# 02_Face_InMain1V0.net
KiCad netlist of a schematic drawn in Altium Designer
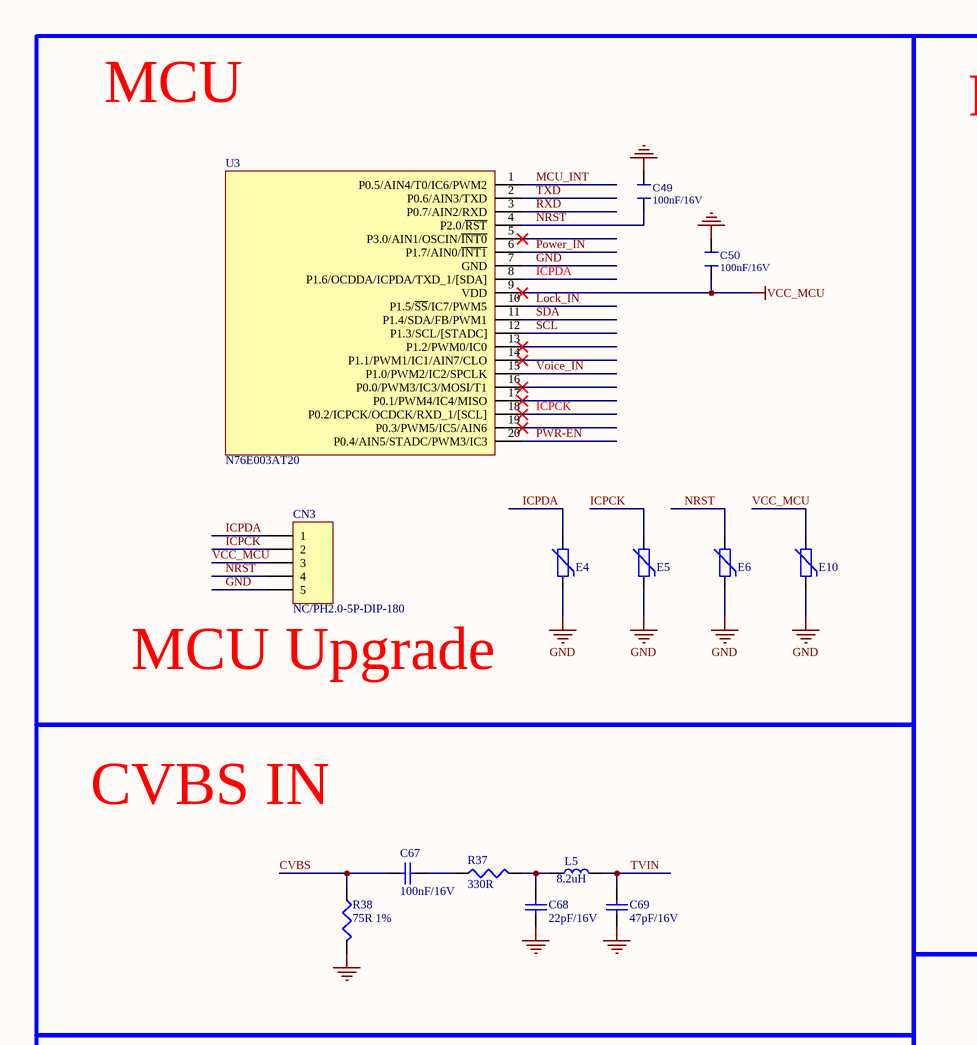
[diagram p0: 02_Face_InMain1V0.SchDoc, top left]
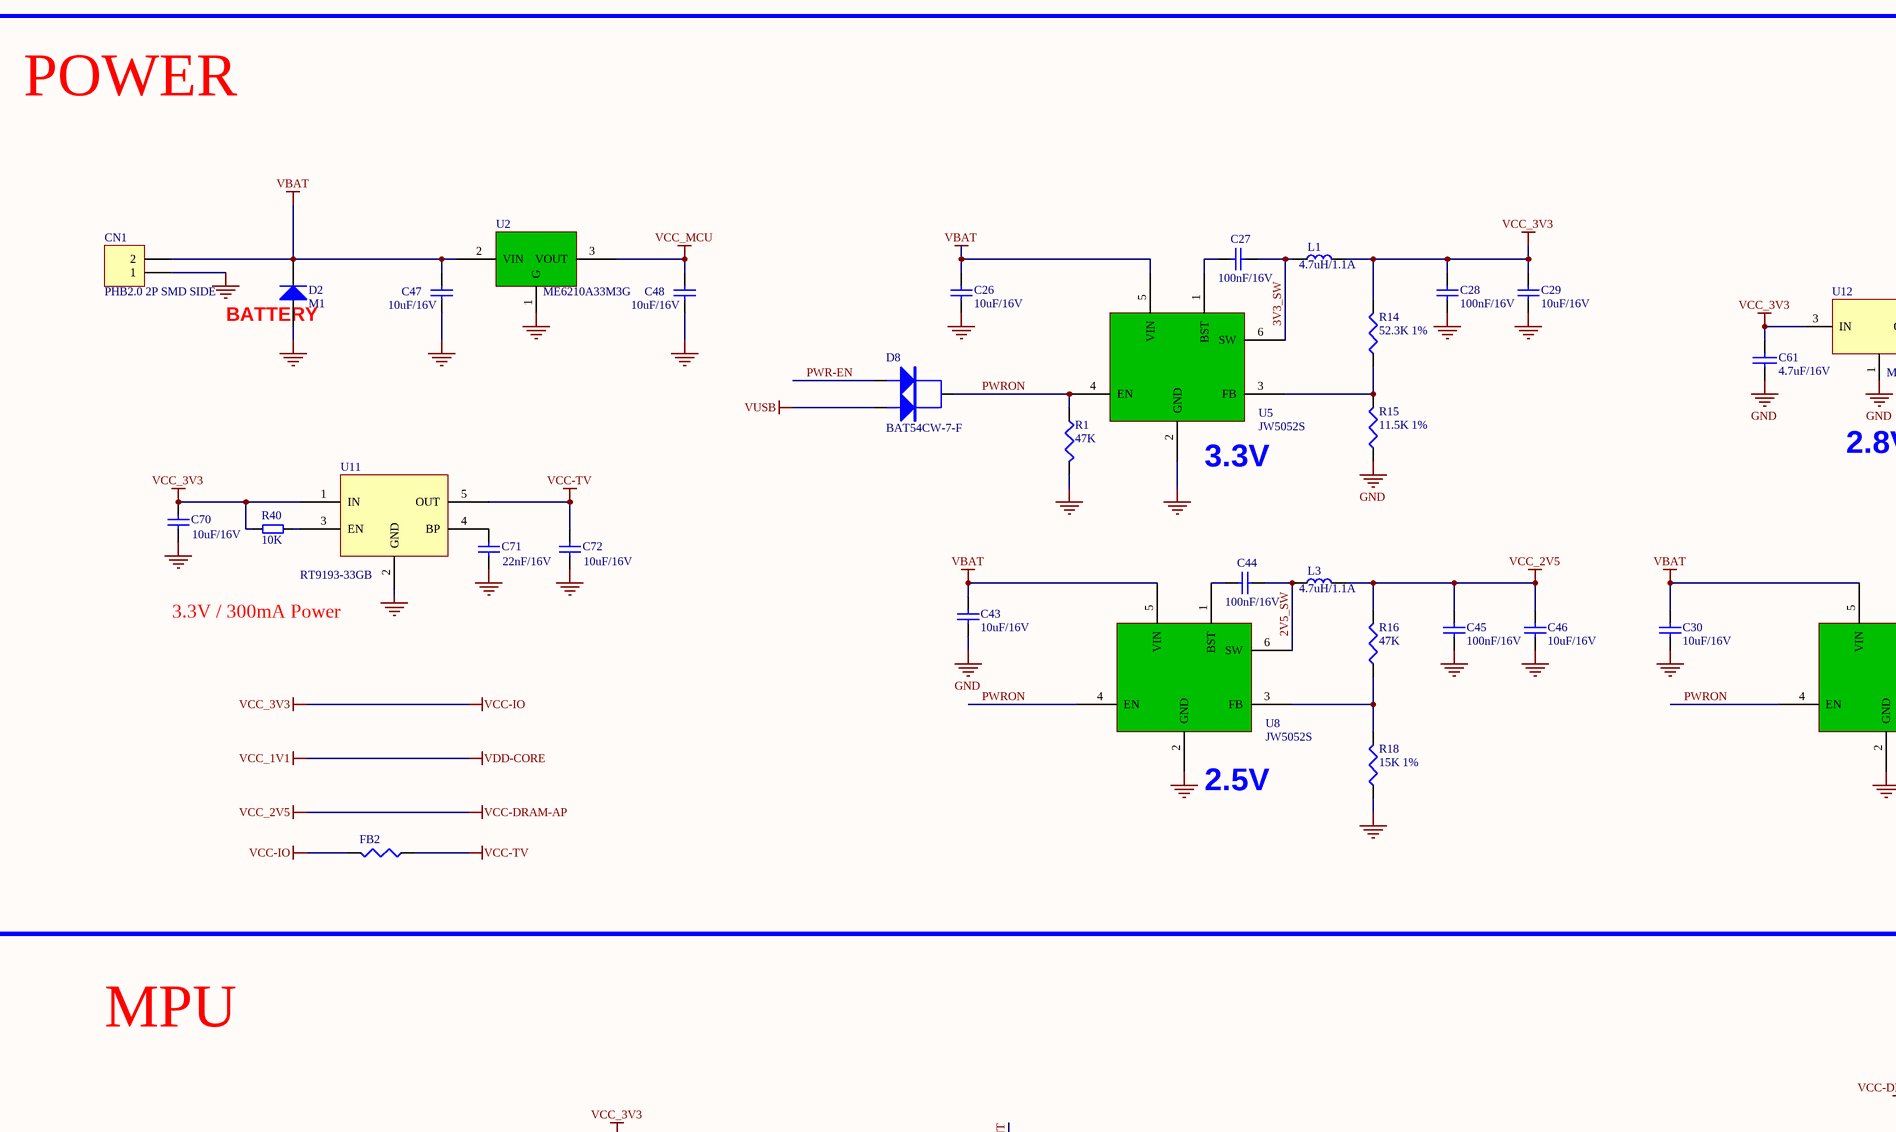
[diagram p1: 02_Face_InMain1V0.SchDoc, top middle]
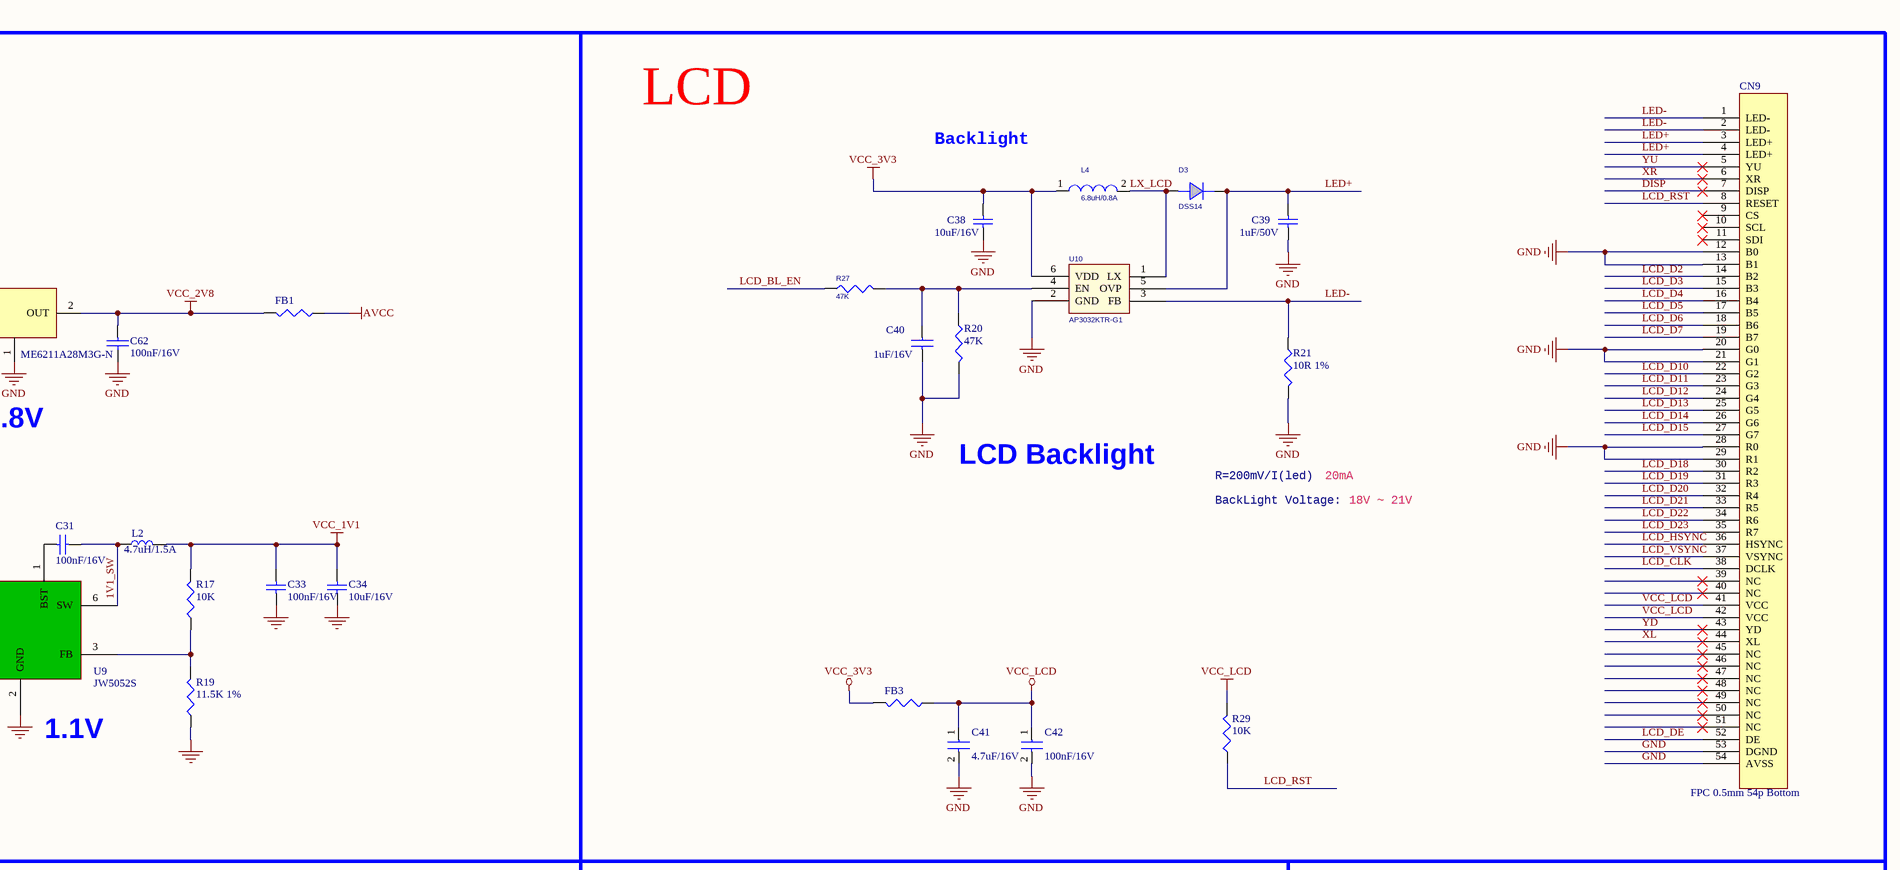
[diagram p2: 02_Face_InMain1V0.SchDoc, top right]
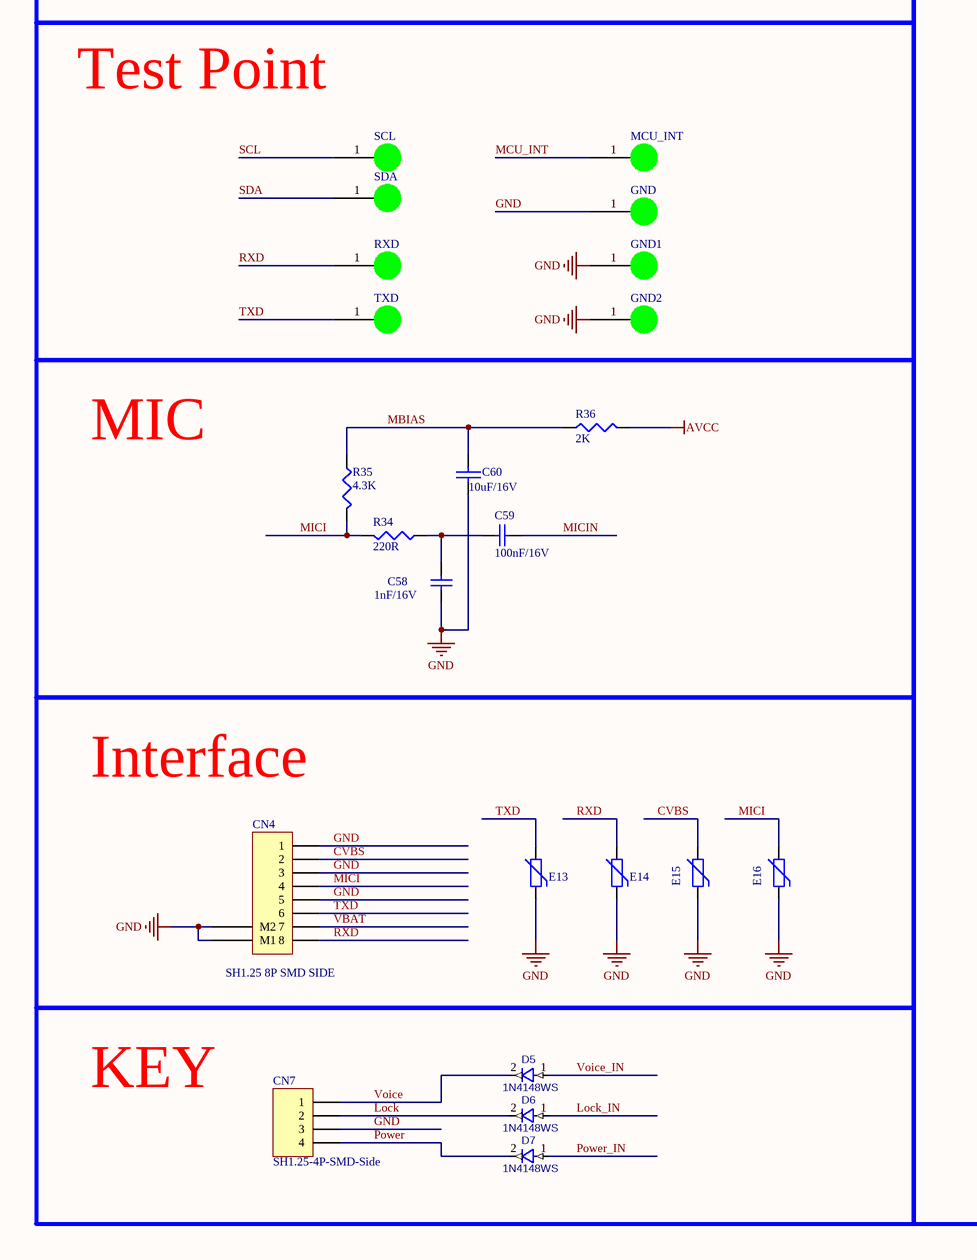
[diagram p3: 02_Face_InMain1V0.SchDoc, bottom left]
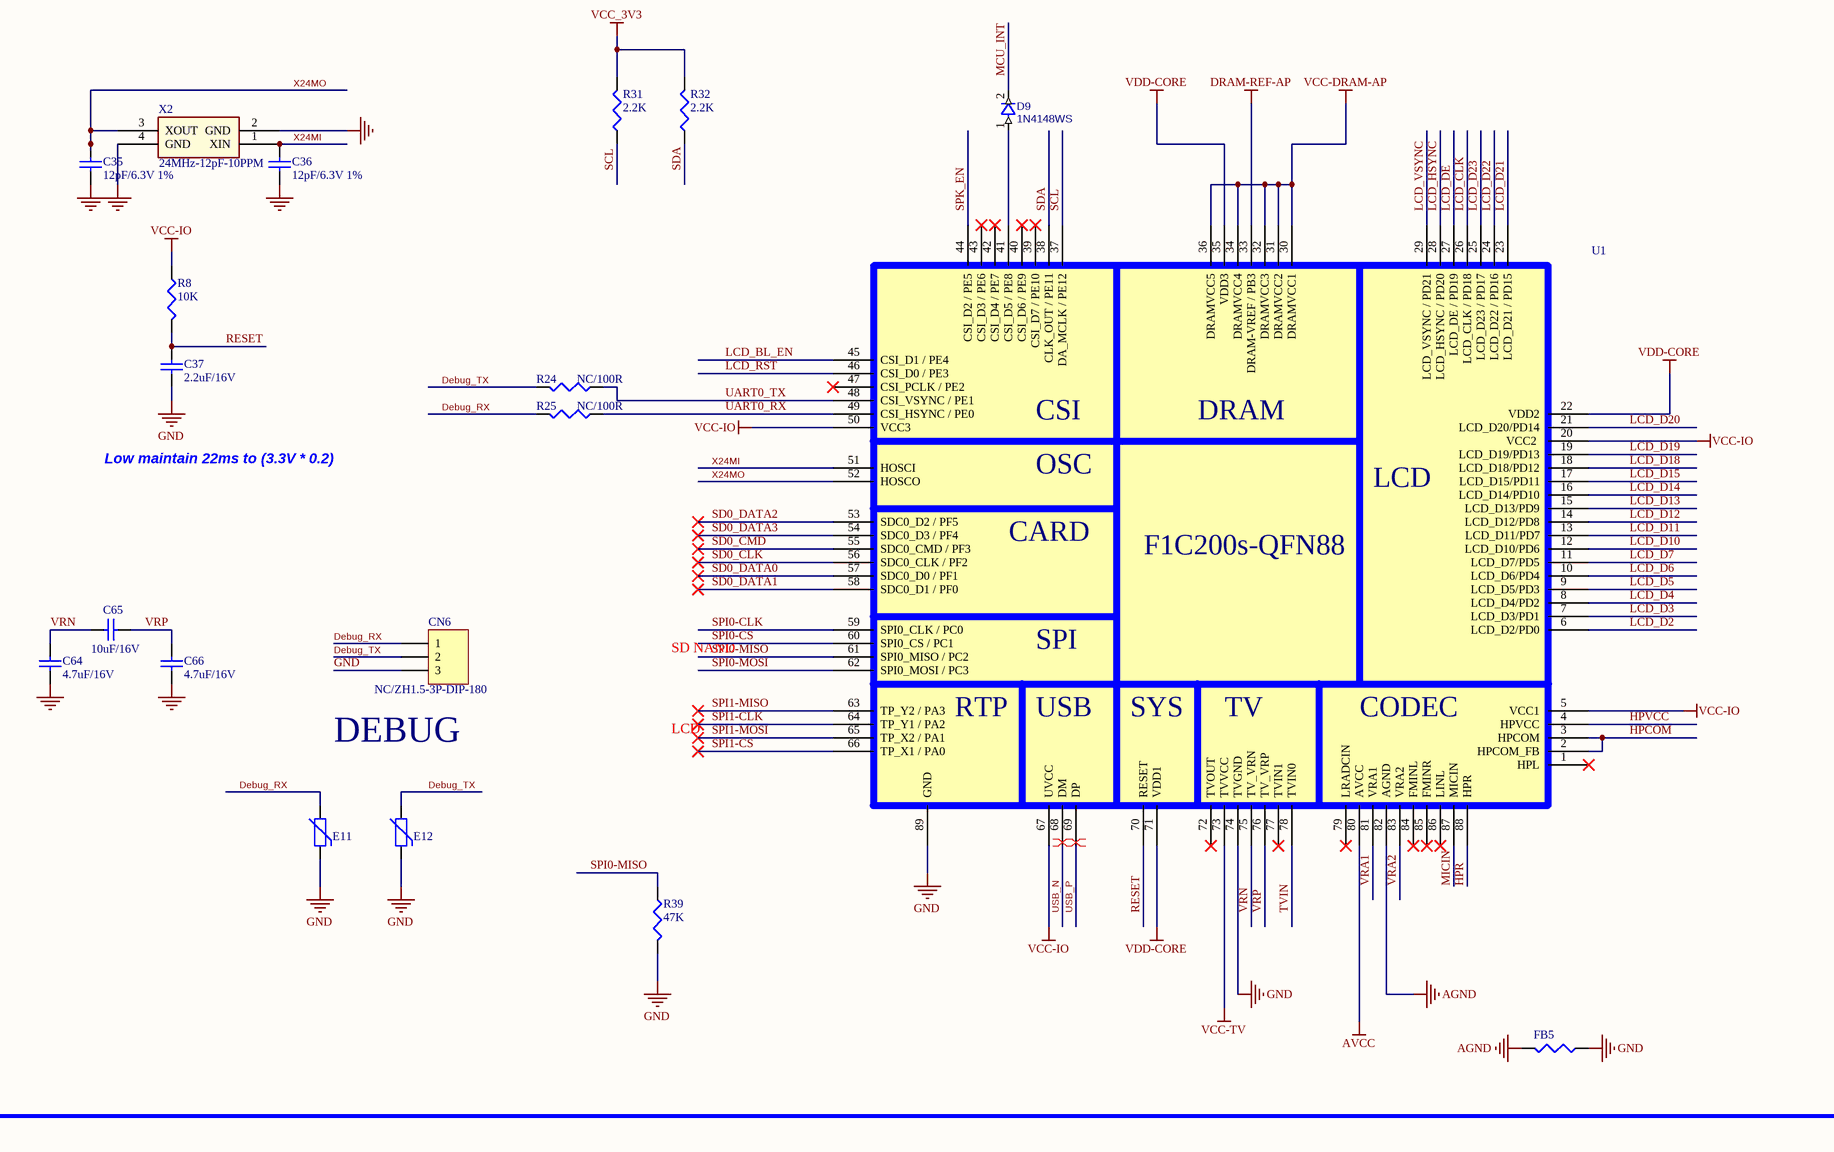
[diagram p4: 02_Face_InMain1V0.SchDoc, bottom middle]
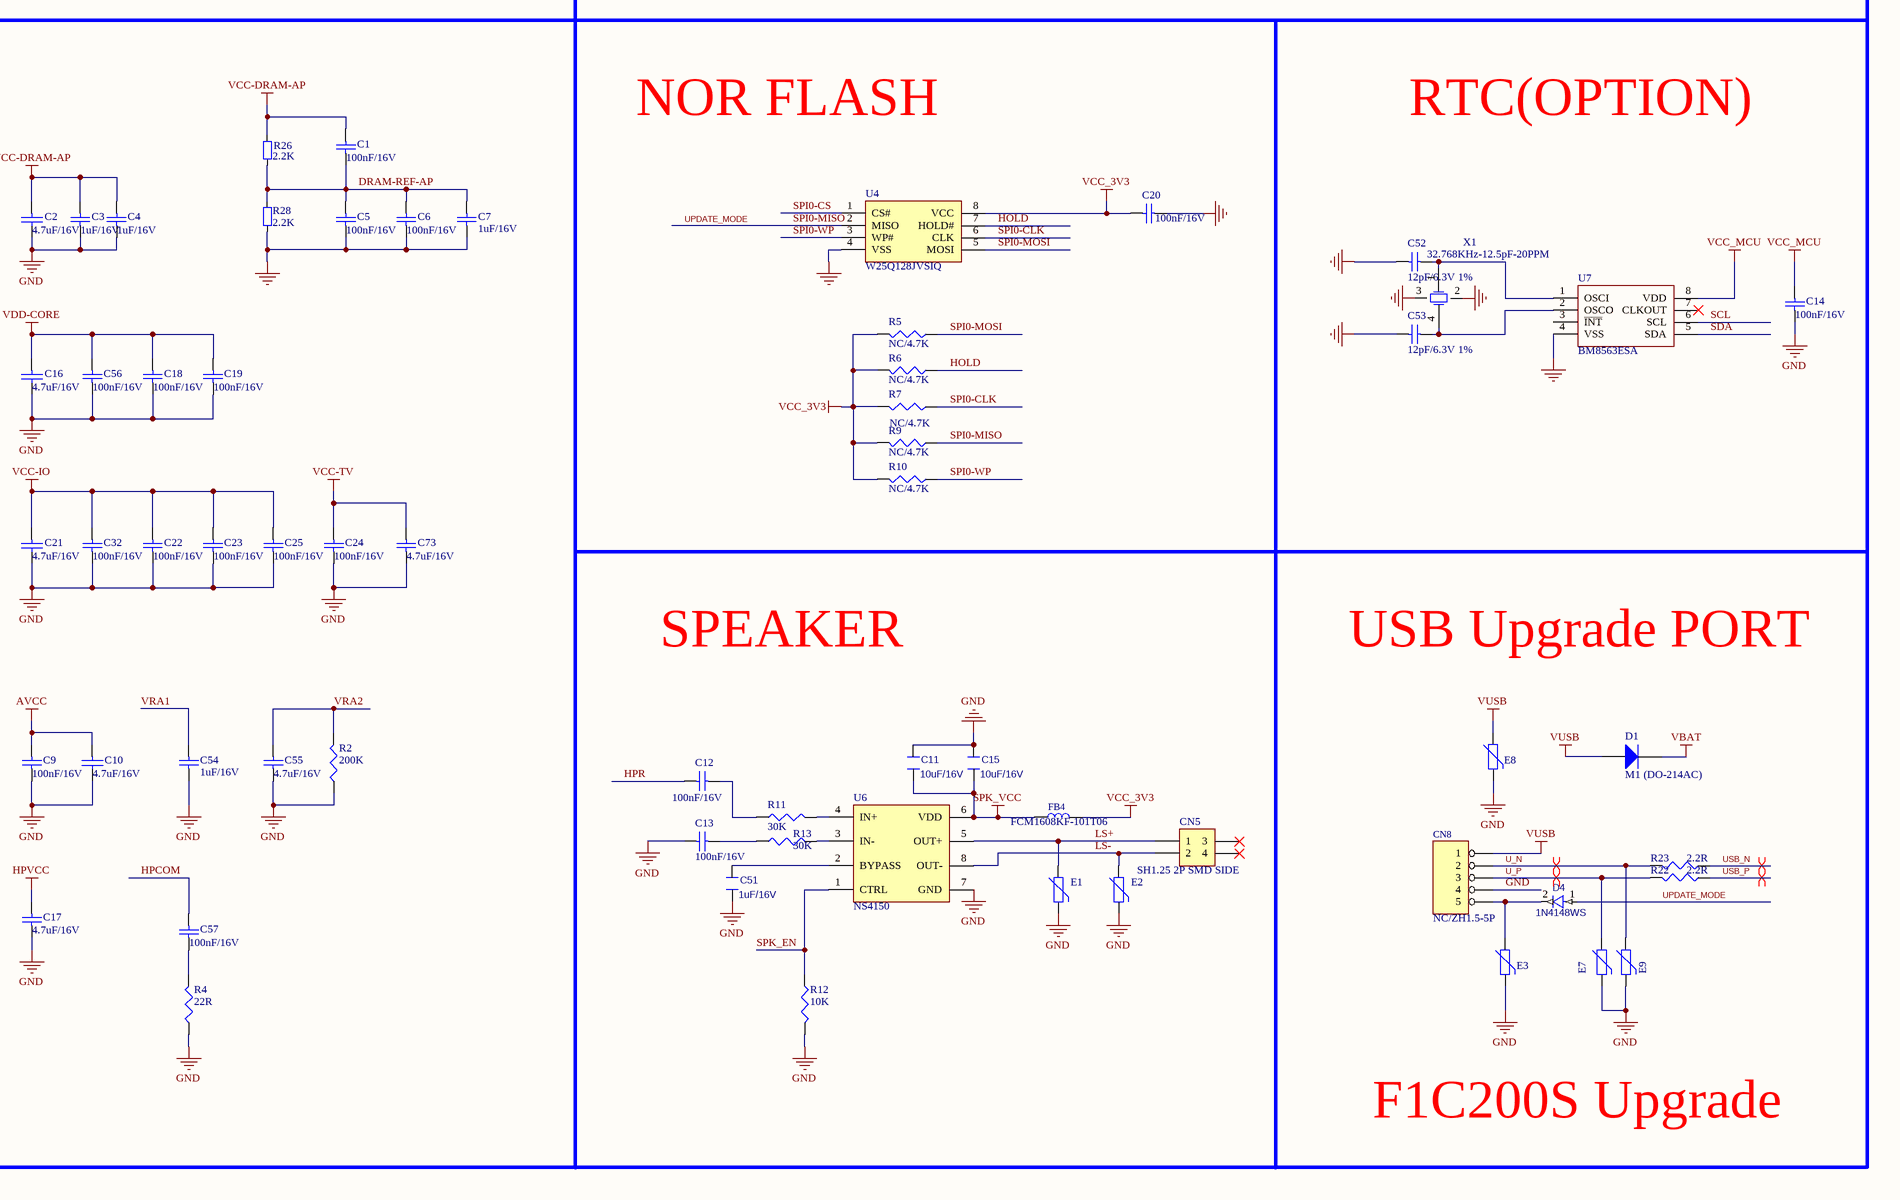
[diagram p5: 02_Face_InMain1V0.SchDoc, bottom right]

(export (version "E")
  (design (tool "Eeschema 10.0.6"))
  (components
    (comp (ref "C1")
      (value "100nF/16V")
      (footprint "C0402")
      (description "0.1uF  ±10% 16V X7R 0402 ROSH")
      (fields (field (name "PUBLISHER") "Altium Limited"))
      (libsource (lib "Miscellaneous Devices") (part "Cap"))
    )
    (comp (ref "C2")
      (value "4.7uF/16V")
      (footprint "C0603")
      (description "4.7uF/16V 10% 0603 X7R ROHS")
      (libsource (lib "*") (part "CAP"))
    )
    (comp (ref "C3")
      (value "1uF/16V")
      (footprint "C0402")
      (description "1uF/16V 10%  0402 X7R ROHS")
      (fields (field (name "PUBLISHER") "Altium Limited"))
      (libsource (lib "Miscellaneous Devices") (part "Cap"))
    )
    (comp (ref "C4")
      (value "1uF/16V")
      (footprint "C0402")
      (description "1uF/16V 10%  0402 X7R ROHS")
      (fields (field (name "PUBLISHER") "Altium Limited"))
      (libsource (lib "Miscellaneous Devices") (part "Cap"))
    )
    (comp (ref "C5")
      (value "100nF/16V")
      (footprint "C0402")
      (description "0.1uF  ±10% 16V X7R 0402 ROHS")
      (fields (field (name "PUBLISHER") "Altium Limited"))
      (libsource (lib "Miscellaneous Devices") (part "Cap"))
    )
    (comp (ref "C6")
      (value "100nF/16V")
      (footprint "C0402")
      (description "0.1uF  ±10% 16V X7R 0402 ROHS")
      (fields (field (name "PUBLISHER") "Altium Limited"))
      (libsource (lib "Miscellaneous Devices") (part "Cap"))
    )
    (comp (ref "C7")
      (value "1uF/16V")
      (footprint "C0402")
      (description "1uF/16V 10%  0402 X7R ROHS")
      (fields (field (name "PUBLISHER") "Altium Limited"))
      (libsource (lib "Miscellaneous Devices") (part "Cap"))
    )
    (comp (ref "C9")
      (value "100nF/16V")
      (footprint "C0402")
      (description "0.1uF  ±10% 16V X7R 0402 ROHS")
      (fields (field (name "PUBLISHER") "Altium Limited"))
      (libsource (lib "Miscellaneous Devices") (part "Cap"))
    )
    (comp (ref "C10")
      (value "4.7uF/16V")
      (footprint "C0603")
      (description "4.7uF/16V 10% 0603 X7R ROHS")
      (libsource (lib "*") (part "CAP"))
    )
    (comp (ref "C11")
      (value "10uF/16V")
      (footprint "C0805")
      (description "10uF/16V 10% 0805 X7R ROHS")
      (libsource (lib "LM") (part "CAP"))
    )
    (comp (ref "C12")
      (value "100nF/16V")
      (footprint "C0402")
      (description "0.1uF  ±10% 16V X7R 0402 ROSH")
      (fields (field (name "PUBLISHER") "Altium Limited"))
      (libsource (lib "Miscellaneous Devices") (part "Cap"))
    )
    (comp (ref "C13")
      (value "100nF/16V")
      (footprint "C0402")
      (description "0.1uF  ±10% 16V X7R 0402 ROSH")
      (fields (field (name "PUBLISHER") "Altium Limited"))
      (libsource (lib "Miscellaneous Devices") (part "Cap"))
    )
    (comp (ref "C14")
      (value "100nF/16V")
      (footprint "C0402")
      (description "0.1uF  ±10% 16V X7R 0402 ROSH")
      (fields (field (name "PUBLISHER") "Altium Limited"))
      (libsource (lib "Miscellaneous Devices") (part "Cap"))
    )
    (comp (ref "C15")
      (value "10uF/16V")
      (footprint "C0805")
      (description "10uF/16V 10% 0805 X7R ROHS")
      (libsource (lib "LM") (part "CAP"))
    )
    (comp (ref "C16")
      (value "4.7uF/16V")
      (footprint "C0603")
      (description "4.7uF/16V 10% 0603 X7R ROHS")
      (libsource (lib "*") (part "CAP"))
    )
    (comp (ref "C17")
      (value "4.7uF/16V")
      (footprint "C0603")
      (description "4.7uF/16V 10% 0603 X7R ROHS")
      (fields (field (name "PUBLISHER") "Altium Limited"))
      (libsource (lib "Miscellaneous Devices") (part "Cap"))
    )
    (comp (ref "C18")
      (value "100nF/16V")
      (footprint "C0402")
      (description "0.1uF  ±10% 16V X7R 0402 ROSH")
      (fields (field (name "PUBLISHER") "Altium Limited"))
      (libsource (lib "Miscellaneous Devices") (part "Cap"))
    )
    (comp (ref "C19")
      (value "100nF/16V")
      (footprint "C0402")
      (description "0.1uF  ±10% 16V X7R 0402 ROSH")
      (fields (field (name "PUBLISHER") "Altium Limited"))
      (libsource (lib "Miscellaneous Devices") (part "Cap"))
    )
    (comp (ref "C20")
      (value "100nF/16V")
      (footprint "C0402")
      (description "0.1uF  ±10% 16V X7R 0402 ROSH")
      (fields (field (name "PUBLISHER") "Altium Limited"))
      (libsource (lib "Miscellaneous Devices") (part "Cap"))
    )
    (comp (ref "C21")
      (value "4.7uF/16V")
      (footprint "C0603")
      (description "4.7uF/16V 10% 0603 X7R ROHS")
      (libsource (lib "*") (part "CAP"))
    )
    (comp (ref "C22")
      (value "100nF/16V")
      (footprint "C0402")
      (description "0.1uF  ±10% 16V X7R 0402 ROSH")
      (fields (field (name "PUBLISHER") "Altium Limited"))
      (libsource (lib "Miscellaneous Devices") (part "Cap"))
    )
    (comp (ref "C23")
      (value "100nF/16V")
      (footprint "C0402")
      (description "0.1uF  ±10% 16V X7R 0402 ROSH")
      (fields (field (name "PUBLISHER") "Altium Limited"))
      (libsource (lib "Miscellaneous Devices") (part "Cap"))
    )
    (comp (ref "C24")
      (value "100nF/16V")
      (footprint "C0402")
      (description "0.1uF  ±10% 16V X7R 0402 ROSH")
      (fields (field (name "PUBLISHER") "Altium Limited"))
      (libsource (lib "Miscellaneous Devices") (part "Cap"))
    )
    (comp (ref "C25")
      (value "100nF/16V")
      (footprint "C0402")
      (description "0.1uF  ±10% 16V X7R 0402 ROSH")
      (fields (field (name "PUBLISHER") "Altium Limited"))
      (libsource (lib "Miscellaneous Devices") (part "Cap"))
    )
    (comp (ref "C26")
      (value "10uF/16V")
      (footprint "C0805")
      (description "10uF/16V 10% 0805 X7R ROHS")
      (fields (field (name "PUBLISHER") "Altium Limited"))
      (libsource (lib "Miscellaneous Devices") (part "Cap"))
    )
    (comp (ref "C27")
      (value "100nF/16V")
      (footprint "C0402")
      (description "0.1uF  ±10% 16V X7R 0402 ROHS")
      (fields (field (name "PUBLISHER") "Altium Limited"))
      (libsource (lib "Miscellaneous Devices") (part "Cap"))
    )
    (comp (ref "C28")
      (value "100nF/16V")
      (footprint "C0402")
      (description "0.1uF  ±10% 16V X7R 0402 ROHS")
      (fields (field (name "PUBLISHER") "Altium Limited"))
      (libsource (lib "Miscellaneous Devices") (part "Cap"))
    )
    (comp (ref "C29")
      (value "10uF/16V")
      (footprint "C0805")
      (description "10uF/16V 10% 0805 X7R ROHS")
      (fields (field (name "PUBLISHER") "Altium Limited"))
      (libsource (lib "Miscellaneous Devices") (part "Cap"))
    )
    (comp (ref "C30")
      (value "10uF/16V")
      (footprint "C0805")
      (description "10uF/16V 10% 0805 X7R ROHS")
      (fields (field (name "PUBLISHER") "Altium Limited"))
      (libsource (lib "Miscellaneous Devices") (part "Cap"))
    )
    (comp (ref "C31")
      (value "100nF/16V")
      (footprint "C0402")
      (description "0.1uF  ±10% 16V X7R 0402 ROHS")
      (fields (field (name "PUBLISHER") "Altium Limited"))
      (libsource (lib "Miscellaneous Devices") (part "Cap"))
    )
    (comp (ref "C32")
      (value "100nF/16V")
      (footprint "C0402")
      (description "0.1uF  ±10% 16V X7R 0402 ROHS")
      (fields (field (name "PUBLISHER") "Altium Limited"))
      (libsource (lib "Miscellaneous Devices") (part "Cap"))
    )
    (comp (ref "C33")
      (value "100nF/16V")
      (footprint "C0402")
      (description "0.1uF  ±10% 16V X7R 0402 ROHS")
      (fields (field (name "PUBLISHER") "Altium Limited"))
      (libsource (lib "Miscellaneous Devices") (part "Cap"))
    )
    (comp (ref "C34")
      (value "10uF/16V")
      (footprint "C0805")
      (description "10uF/16V 10% 0805 X7R ROHS")
      (fields (field (name "PUBLISHER") "Altium Limited"))
      (libsource (lib "Miscellaneous Devices") (part "Cap"))
    )
    (comp (ref "C35")
      (value "12pF/6.3V 1%")
      (footprint "C0402")
      (description "12pF/6.3V 2% 0402 NPO ROHS")
      (fields (field (name "PUBLISHER") "Altium Limited"))
      (libsource (lib "Miscellaneous Devices") (part "Cap"))
    )
    (comp (ref "C36")
      (value "12pF/6.3V 1%")
      (footprint "C0402")
      (description "12pF/6.3V 2% 0402 NPO ROHS")
      (fields (field (name "PUBLISHER") "Altium Limited"))
      (libsource (lib "Miscellaneous Devices") (part "Cap"))
    )
    (comp (ref "C37")
      (value "2.2uF/16V")
      (footprint "C0402")
      (description "2.2uF/16V 10%  0402 X7R ROHS")
      (fields (field (name "PUBLISHER") "Altium Limited"))
      (libsource (lib "Miscellaneous Devices") (part "Cap"))
    )
    (comp (ref "C38")
      (value "10uF/16V")
      (footprint "C0805")
      (description "10uF/16V 10% 0805 X7R ROHS")
      (fields (field (name "PUBLISHER") "Altium Limited"))
      (libsource (lib "Miscellaneous Devices") (part "Cap"))
    )
    (comp (ref "C39")
      (value "1uF/50V")
      (footprint "C0805")
      (description "1uF/50V 10% 0805 X7R ROHS")
      (fields (field (name "PUBLISHER") "Altium Limited"))
      (libsource (lib "Miscellaneous Devices") (part "Cap"))
    )
    (comp (ref "C40")
      (value "1uF/16V")
      (footprint "C0402")
      (description "1uF/16V 10%  0402 X7R ROHS")
      (fields
        (field (name "VOLTAGE") "6.3V")
        (field (name "TOLERANCE") "10%")
        (field (name "CREATED BY") "JJJ")
      )
      (libsource (lib "") (part "CAP NP_Dup1_1"))
    )
    (comp (ref "C41")
      (value "4.7uF/16V")
      (footprint "C0603")
      (description "4.7uF/16V 10% 0603 X7R ROHS")
      (fields
        (field (name "VOLTAGE") "6.3V")
        (field (name "TOLERANCE") "10%")
        (field (name "CREATED BY") "JJJ")
      )
      (libsource (lib "*") (part "CAP NP_Dup1"))
    )
    (comp (ref "C42")
      (value "100nF/16V")
      (footprint "C0402")
      (description "0.1uF  ±10% 16V X7R 0402 ROHS")
      (fields
        (field (name "VOLTAGE") "6.3V")
        (field (name "TOLERANCE") "10%")
        (field (name "CREATED BY") "JJJ")
      )
      (libsource (lib "*") (part "CAP NP_Dup1"))
    )
    (comp (ref "C43")
      (value "10uF/16V")
      (footprint "C0805")
      (description "10uF/16V 10% 0805 X7R ROHS")
      (fields (field (name "PUBLISHER") "Altium Limited"))
      (libsource (lib "Miscellaneous Devices") (part "Cap"))
    )
    (comp (ref "C44")
      (value "100nF/16V")
      (footprint "C0402")
      (description "0.1uF  ±10% 16V X7R 0402 ROHS")
      (fields (field (name "PUBLISHER") "Altium Limited"))
      (libsource (lib "Miscellaneous Devices") (part "Cap"))
    )
    (comp (ref "C45")
      (value "100nF/16V")
      (footprint "C0402")
      (description "0.1uF  ±10% 16V X7R 0402 ROHS")
      (fields (field (name "PUBLISHER") "Altium Limited"))
      (libsource (lib "Miscellaneous Devices") (part "Cap"))
    )
    (comp (ref "C46")
      (value "10uF/16V")
      (footprint "C0805")
      (description "10uF/16V 10% 0805 X7R ROHS")
      (fields (field (name "PUBLISHER") "Altium Limited"))
      (libsource (lib "Miscellaneous Devices") (part "Cap"))
    )
    (comp (ref "C47")
      (value "10uF/16V")
      (footprint "C0805")
      (description "10uF/16V 10% 0805 X7R ROHS")
      (fields (field (name "PUBLISHER") "Altium Limited"))
      (libsource (lib "Miscellaneous Devices") (part "Cap"))
    )
    (comp (ref "C48")
      (value "10uF/16V")
      (footprint "C0805")
      (description "10uF/16V 10% 0805 X7R ROHS")
      (fields (field (name "PUBLISHER") "Altium Limited"))
      (libsource (lib "Miscellaneous Devices") (part "Cap"))
    )
    (comp (ref "C49")
      (value "100nF/16V")
      (footprint "C0402")
      (description "0.1uF  ±10% 16V X7R 0402 ROHS")
      (fields (field (name "ALTIUM_UNNAMED_1") "100nF/16V"))
      (libsource (lib "LM") (part "CAP"))
    )
    (comp (ref "C50")
      (value "100nF/16V")
      (footprint "C0402")
      (description "0.1uF  ±10% 16V X7R 0402 ROHS")
      (fields (field (name "ALTIUM_UNNAMED_1") "100nF/16V"))
      (libsource (lib "LM") (part "CAP"))
    )
    (comp (ref "C51")
      (value "1uF/16V")
      (footprint "C0402")
      (description "1uF ±10% 16V X7R 0402 ROSH")
      (libsource (lib "LM") (part "CAP"))
    )
    (comp (ref "C52")
      (value "12pF/6.3V 1%")
      (footprint "C0402")
      (description "12pF/6.3V 2% 0402 NPO ROHS")
      (fields (field (name "PUBLISHER") "Altium Limited"))
      (libsource (lib "Miscellaneous Devices") (part "Cap"))
    )
    (comp (ref "C53")
      (value "12pF/6.3V 1%")
      (footprint "C0402")
      (description "12pF/6.3V 2% 0402 NPO ROHS")
      (fields (field (name "PUBLISHER") "Altium Limited"))
      (libsource (lib "Miscellaneous Devices") (part "Cap"))
    )
    (comp (ref "C54")
      (value "1uF/16V")
      (footprint "C0402")
      (description "1uF/16V 10%  0402 X7R ROHS")
      (fields (field (name "PUBLISHER") "Altium Limited"))
      (libsource (lib "Miscellaneous Devices") (part "Cap"))
    )
    (comp (ref "C55")
      (value "4.7uF/16V")
      (footprint "C0603")
      (description "4.7uF/16V 10% 0603 X7R ROHS")
      (fields (field (name "PUBLISHER") "Altium Limited"))
      (libsource (lib "Miscellaneous Devices") (part "Cap"))
    )
    (comp (ref "C56")
      (value "100nF/16V")
      (footprint "C0402")
      (description "0.1uF  ±10% 16V X7R 0402 ROHS")
      (fields (field (name "PUBLISHER") "Altium Limited"))
      (libsource (lib "Miscellaneous Devices") (part "Cap"))
    )
    (comp (ref "C57")
      (value "100nF/16V")
      (footprint "C0402")
      (description "0.1uF  ±10% 16V X7R 0402 ROHS")
      (fields (field (name "PUBLISHER") "Altium Limited"))
      (libsource (lib "Miscellaneous Devices") (part "Cap"))
    )
    (comp (ref "C58")
      (value "1nF/16V")
      (footprint "C0402")
      (description "1nF  ±10% 16V X7R 0402 ROHS")
      (fields (field (name "PUBLISHER") "Altium Limited"))
      (libsource (lib "Miscellaneous Devices") (part "Cap"))
    )
    (comp (ref "C59")
      (value "100nF/16V")
      (footprint "C0402")
      (description "0.1uF  ±10% 16V X7R 0402 ROHS")
      (fields (field (name "PUBLISHER") "Altium Limited"))
      (libsource (lib "Miscellaneous Devices") (part "Cap"))
    )
    (comp (ref "C60")
      (value "10uF/16V")
      (footprint "C0805")
      (description "10uF/16V 10% 0805 X7R ROHS")
      (libsource (lib "*") (part "CAP"))
    )
    (comp (ref "C61")
      (value "4.7uF/16V")
      (footprint "C0603")
      (description "4.7uF/16V 10% 0603 X7R ROHS")
      (libsource (lib "FL01M1V5") (part "CAP"))
    )
    (comp (ref "C62")
      (value "100nF/16V")
      (footprint "C0402")
      (description "100nF/16V 10% 0402 X7R ROHS")
      (libsource (lib "FL01M1V5") (part "CAP"))
    )
    (comp (ref "C64")
      (value "4.7uF/16V")
      (footprint "C0603")
      (description "4.7uF/16V 10% 0603 X7R ROHS")
      (fields (field (name "PUBLISHER") "Altium Limited"))
      (libsource (lib "Miscellaneous Devices") (part "Cap"))
    )
    (comp (ref "C65")
      (value "10uF/16V")
      (footprint "C0805")
      (description "10uF/16V 10% 0805 X7R ROHS")
      (fields (field (name "PUBLISHER") "Altium Limited"))
      (libsource (lib "Miscellaneous Devices") (part "Cap"))
    )
    (comp (ref "C66")
      (value "4.7uF/16V")
      (footprint "C0603")
      (description "4.7uF/16V 10% 0603 X7R ROHS")
      (fields (field (name "PUBLISHER") "Altium Limited"))
      (libsource (lib "Miscellaneous Devices") (part "Cap"))
    )
    (comp (ref "C67")
      (value "100nF/16V")
      (footprint "C0402")
      (description "100nF/16V 10% 0402 X7R ROHS")
      (fields (field (name "PUBLISHER") "Altium Limited"))
      (libsource (lib "Miscellaneous Devices") (part "Cap"))
    )
    (comp (ref "C68")
      (value "22pF/16V")
      (footprint "C0402")
      (description "22pF/16V 10% 0402 X7R ROHS")
      (fields (field (name "PUBLISHER") "Altium Limited"))
      (libsource (lib "Miscellaneous Devices") (part "Cap"))
    )
    (comp (ref "C69")
      (value "47pF/16V")
      (footprint "C0402")
      (description "47pF/16V 10% 0402 X7R ROHS")
      (fields (field (name "PUBLISHER") "Altium Limited"))
      (libsource (lib "Miscellaneous Devices") (part "Cap"))
    )
    (comp (ref "C70")
      (value "10uF/16V")
      (footprint "C0805")
      (description "10uF/16V 10% 0805 X7R ROHS")
      (fields (field (name "PUBLISHER") "Altium Limited"))
      (libsource (lib "Miscellaneous Devices") (part "Cap"))
    )
    (comp (ref "C71")
      (value "22nF/16V")
      (footprint "C0402")
      (description "22nF/16V 10% 0402 X7R ROHS")
      (fields (field (name "PUBLISHER") "Altium Limited"))
      (libsource (lib "Miscellaneous Devices") (part "Cap"))
    )
    (comp (ref "C72")
      (value "10uF/16V")
      (footprint "C0805")
      (description "10uF/16V 10% 0805 X7R ROHS")
      (fields (field (name "PUBLISHER") "Altium Limited"))
      (libsource (lib "Miscellaneous Devices") (part "Cap"))
    )
    (comp (ref "C73")
      (value "4.7uF/16V")
      (footprint "C0603")
      (description "4.7uF/16V 10% 0603 X7R ROHS")
      (fields (field (name "PUBLISHER") "Altium Limited"))
      (libsource (lib "Miscellaneous Devices") (part "Cap"))
    )
    (comp (ref "CN1")
      (value "PHB2.0 2P SMD SIDE")
      (footprint "PH2.0_2P_SMD_SIDE")
      (description "PHB2.0 2P 90")
      (fields (field (name "PUBLISHER") "Altium Limited"))
      (libsource (lib "Miscellaneous Connectors") (part "Header 2"))
    )
    (comp (ref "CN3")
      (value "NC/PH2.0-5P-DIP-180")
      (footprint "HD2.0_5P")
      (description "PH2.0-5P-DIP-180")
      (fields (field (name "NAME1") "NC/PH2.0-5P-DIP-180"))
      (libsource (lib "LM") (part "Header5"))
    )
    (comp (ref "CN4")
      (value "SH1.25 8P SMD SIDE")
      (footprint "SH1.25_8P_SMD_SIDE")
      (description "FPC8_0.5")
      (fields (field (name "PUBLISHER") "Altium Limited"))
      (libsource (lib "S6X_1V0") (part "Header 8"))
    )
    (comp (ref "CN5")
      (value "SH1.25 2P SMD SIDE")
      (footprint "SH1.25_2P_SMD_SIDE")
      (libsource (lib "S8Main2V0") (part "Header2"))
    )
    (comp (ref "CN6")
      (value "NC/ZH1.5 3P")
      (footprint "HD1.5_3P")
      (description "ZH1.5mm 3P")
      (fields (field (name "NAME1") "NC/ZH1.5-3P-DIP-180"))
      (libsource (lib "LM") (part "Header3"))
    )
    (comp (ref "CN7")
      (value "SH1.25-4P-SMD-TOP")
      (footprint "SH1.25_4P_SMd_SIDE")
      (fields (field (name "NAME1") "SH1.25-4P-SMD-Side"))
      (libsource (lib "LM") (part "Header4"))
    )
    (comp (ref "CN8")
      (value "NC/ZH1.5-5P")
      (footprint "HD5_1.5")
      (description "ZH1.5mm 5P")
      (libsource (lib "*") (part "HEADER 5"))
    )
    (comp (ref "CN9")
      (value "FPC 0.5mm 54p Bottom")
      (footprint "FPC54_0.5_BOTTOM_Clamshell-1")
      (libsource (lib "*") (part "CON54"))
    )
    (comp (ref "D1")
      (value "M1 (DO-214AC)")
      (footprint "DO-214AC")
      (libsource (lib "LM") (part "M2 (DO-214AC)"))
    )
    (comp (ref "D2")
      (value "M1 (DO-214AC)")
      (footprint "DO-214AC")
      (fields (field (name "ALTIUM_UNNAMED_1") "M1"))
      (libsource (lib "LM") (part "M2 (DO-214AC)"))
    )
    (comp (ref "D3") (value "DSS14") (footprint "SOD-123FL") (libsource (lib "*") (part "D_0")))
    (comp (ref "D4")
      (value "1N4148WS")
      (footprint "SOD-323")
      (description "1N4148WS (SOD-323)")
      (libsource (lib "*") (part "1N4500"))
    )
    (comp (ref "D5")
      (value "1N4148WS")
      (footprint "SOD-323")
      (description "1N4148WS (SOD-323)")
      (libsource (lib "*") (part "1N4500"))
    )
    (comp (ref "D6")
      (value "1N4148WS")
      (footprint "SOD-323")
      (description "1N4148WS (SOD-323)")
      (libsource (lib "*") (part "1N4500"))
    )
    (comp (ref "D7")
      (value "1N4148WS")
      (footprint "SOD-323")
      (description "1N4148WS (SOD-323)")
      (libsource (lib "*") (part "1N4500"))
    )
    (comp (ref "D8")
      (value "BAT54CW-7-F (SOT-323)")
      (footprint "sot323")
      (fields (field (name "ALTIUM_UNNAMED_1") "BAT54CW-7-F"))
      (libsource (lib "LM") (part "BAT54CW-KL7"))
    )
    (comp (ref "D9")
      (value "1N4148WS")
      (footprint "SOD-323")
      (description "1N4148WS (SOD-323)")
      (libsource (lib "*") (part "1N4500"))
    )
    (comp (ref "E1")
      (value "SFI0402-050E330NP-LF")
      (footprint "R0402")
      (libsource (lib "ZhuhaiSch") (part "VARISTOR"))
    )
    (comp (ref "E2")
      (value "SFI0402-050E330NP-LF")
      (footprint "R0402")
      (libsource (lib "ZhuhaiSch") (part "VARISTOR"))
    )
    (comp (ref "E3")
      (value "SFI0402-050E330NP-LF")
      (footprint "R0402")
      (libsource (lib "ZhuhaiSch") (part "VARISTOR"))
    )
    (comp (ref "E4")
      (value "SFI0402-050E330NP-LF")
      (footprint "R0402")
      (libsource (lib "ZhuhaiSch") (part "VARISTOR"))
    )
    (comp (ref "E5")
      (value "SFI0402-050E330NP-LF")
      (footprint "R0402")
      (libsource (lib "ZhuhaiSch") (part "VARISTOR"))
    )
    (comp (ref "E6")
      (value "SFI0402-050E330NP-LF")
      (footprint "R0402")
      (libsource (lib "ZhuhaiSch") (part "VARISTOR"))
    )
    (comp (ref "E7")
      (value "SLESDL0402-24")
      (footprint "R0402")
      (libsource (lib "ZhuhaiSch") (part "VARISTOR"))
    )
    (comp (ref "E8")
      (value "SFI0402-050E330NP-LF")
      (footprint "R0402")
      (libsource (lib "ZhuhaiSch") (part "VARISTOR"))
    )
    (comp (ref "E9")
      (value "SLESDL0402-24")
      (footprint "R0402")
      (libsource (lib "ZhuhaiSch") (part "VARISTOR"))
    )
    (comp (ref "E10")
      (value "SFI0402-050E330NP-LF")
      (footprint "R0402")
      (libsource (lib "ZhuhaiSch") (part "VARISTOR"))
    )
    (comp (ref "E11")
      (value "NC/SFI0402-050E330NP-LF")
      (footprint "R0402")
      (description "SFI0402-050E330NP-LF")
      (libsource (lib "ZhuhaiSch") (part "VARISTOR"))
    )
    (comp (ref "E12")
      (value "NC/SFI0402-050E330NP-LF")
      (footprint "R0402")
      (description "SFI0402-050E330NP-LF")
      (libsource (lib "ZhuhaiSch") (part "VARISTOR"))
    )
    (comp (ref "E13")
      (value "SFI0402-050E330NP-LF")
      (footprint "R0402")
      (libsource (lib "ZhuhaiSch") (part "VARISTOR"))
    )
    (comp (ref "E14")
      (value "SFI0402-050E330NP-LF")
      (footprint "R0402")
      (libsource (lib "ZhuhaiSch") (part "VARISTOR"))
    )
    (comp (ref "E15")
      (value "SLESDL0402-24")
      (footprint "R0402")
      (libsource (lib "ZhuhaiSch") (part "VARISTOR"))
    )
    (comp (ref "E16")
      (value "SLESDL0402-24")
      (footprint "R0402")
      (libsource (lib "ZhuhaiSch") (part "VARISTOR"))
    )
    (comp (ref "FB1")
      (value "FB_100R")
      (footprint "R0603")
      (description "FCM1608KF-101T06")
      (fields
        (field (name "TOLERANCE") "5%")
        (field (name "MANUFACTURER") "YAGEO")
        (field (name "CREATED BY") "YTL")
      )
      (libsource (lib "*") (part "RESISTOR_Dup1"))
    )
    (comp (ref "FB2")
      (value "NC/FB_100R")
      (footprint "R0603")
      (description "FCM1608KF-101T06")
      (fields
        (field (name "TOLERANCE") "5%")
        (field (name "MANUFACTURER") "YAGEO")
        (field (name "CREATED BY") "YTL")
      )
      (libsource (lib "*") (part "RESISTOR_Dup1"))
    )
    (comp (ref "FB3")
      (value "FB_100R")
      (footprint "R0603")
      (description "FCM1608KF-101T06")
      (fields
        (field (name "TOLERANCE") "5%")
        (field (name "MANUFACTURER") "YAGEO")
        (field (name "CREATED BY") "YTL")
      )
      (libsource (lib "*") (part "RESISTOR_Dup1"))
    )
    (comp (ref "FB4") (value "FCM1608KF-101T06") (footprint "R0603") (libsource (lib "LM") (part "INDUCTOR")))
    (comp (ref "FB5")
      (value "FB_100R")
      (footprint "R0603")
      (description "FCM1608KF-101T06")
      (fields
        (field (name "TOLERANCE") "5%")
        (field (name "MANUFACTURER") "YAGEO")
        (field (name "CREATED BY") "YTL")
      )
      (libsource (lib "*") (part "RESISTOR_Dup1"))
    )
    (comp (ref "GND")
      (value "Test Point")
      (footprint "Test Point")
      (libsource (lib "VD_DES3V0") (part "Test Point"))
    )
    (comp (ref "GND1")
      (value "Test Point")
      (footprint "Test Pad")
      (libsource (lib "VD_DES3V0") (part "Test Point"))
    )
    (comp (ref "GND2")
      (value "Test Point")
      (footprint "Test Pad")
      (libsource (lib "VD_DES3V0") (part "Test Point"))
    )
    (comp (ref "L1")
      (value "4.7uH/1.1A")
      (footprint "CD32")
      (description "SWPA3015S4R7MT(4.7uH@1.1A DCR<0.125R)")
      (libsource (lib "FL01M1V5") (part "Inductor"))
    )
    (comp (ref "L2")
      (value "4.7uH/1.5A")
      (footprint "CD32")
      (description "SWPA3015S4R7MT(4.7uH@1.1A DCR<0.125R)")
      (libsource (lib "FL01M1V5") (part "Inductor"))
    )
    (comp (ref "L3")
      (value "4.7uH/1.1A")
      (footprint "CD32")
      (description "SWPA3015S4R7MT(4.7uH@1.1A DCR<0.125R)")
      (libsource (lib "FL01M1V5") (part "Inductor"))
    )
    (comp (ref "L4")
      (value "6.8uH/0.8A")
      (footprint "CD32")
      (description "SWPA3015S6R8MT(6.8uH@0.85A DCR<0.200R)")
      (libsource (lib "*") (part "INDUCTOR_Dup1"))
    )
    (comp (ref "L5")
      (value "8.2uH")
      (footprint "R0603")
      (description "SDFL1608S8R2KTF(8.2uH@5mA DCR<2.1R)")
      (libsource (lib "S10_5V1") (part "Inductor"))
    )
    (comp (ref "MCU_INT")
      (value "Test Point")
      (footprint "Test Point")
      (libsource (lib "VD_DES3V0") (part "Test Point"))
    )
    (comp (ref "R1")
      (value "47K")
      (footprint "R0402")
      (description "47K +/-1% 1/16W 0402 ROHS")
      (fields
        (field (name "TOLERANCE") "5%")
        (field (name "MANUFACTURER") "YAGEO")
        (field (name "CREATED BY") "YTL")
      )
      (libsource (lib "*") (part "RESISTOR_Dup1"))
    )
    (comp (ref "R2")
      (value "200K")
      (footprint "R0402")
      (description "200K +/-5% 1/16W 0402 ROHS")
      (fields
        (field (name "TOLERANCE") "5%")
        (field (name "MANUFACTURER") "YAGEO")
        (field (name "CREATED BY") "YTL")
      )
      (libsource (lib "*") (part "RESISTOR_Dup1"))
    )
    (comp (ref "R4")
      (value "22R")
      (footprint "R0402")
      (description "22R +/-5% 1/16W 0402 ROHS")
      (fields
        (field (name "TOLERANCE") "5%")
        (field (name "MANUFACTURER") "YAGEO")
        (field (name "CREATED BY") "YTL")
      )
      (libsource (lib "*") (part "RESISTOR_Dup1"))
    )
    (comp (ref "R5")
      (value "NC/4.7K")
      (footprint "R0402")
      (description "4.7K +/-5% 1/16W 0402 ROHS")
      (fields
        (field (name "TOLERANCE") "5%")
        (field (name "MANUFACTURER") "YAGEO")
        (field (name "CREATED BY") "YTL")
      )
      (libsource (lib "*") (part "RESISTOR_Dup1"))
    )
    (comp (ref "R6")
      (value "NC/4.7K")
      (footprint "R0402")
      (description "4.7K +/-5% 1/16W 0402 ROHS")
      (fields
        (field (name "TOLERANCE") "5%")
        (field (name "MANUFACTURER") "YAGEO")
        (field (name "CREATED BY") "YTL")
      )
      (libsource (lib "*") (part "RESISTOR_Dup1"))
    )
    (comp (ref "R7")
      (value "NC/4.7K")
      (footprint "R0402")
      (description "4.7K +/-5% 1/16W 0402 ROHS")
      (fields
        (field (name "TOLERANCE") "5%")
        (field (name "MANUFACTURER") "YAGEO")
        (field (name "CREATED BY") "YTL")
      )
      (libsource (lib "*") (part "RESISTOR_Dup1"))
    )
    (comp (ref "R8")
      (value "10K")
      (footprint "R0402")
      (description "10K +/-1% 1/16W 0402 ROHS")
      (fields
        (field (name "TOLERANCE") "5%")
        (field (name "MANUFACTURER") "YAGEO")
        (field (name "CREATED BY") "YTL")
      )
      (libsource (lib "*") (part "RESISTOR_Dup1"))
    )
    (comp (ref "R9")
      (value "NC/4.7K")
      (footprint "R0402")
      (description "4.7K +/-5% 1/16W 0402 ROHS")
      (fields
        (field (name "TOLERANCE") "5%")
        (field (name "MANUFACTURER") "YAGEO")
        (field (name "CREATED BY") "YTL")
      )
      (libsource (lib "*") (part "RESISTOR_Dup1"))
    )
    (comp (ref "R10")
      (value "NC/4.7K")
      (footprint "R0402")
      (description "4.7K +/-5% 1/16W 0402 ROHS")
      (fields
        (field (name "TOLERANCE") "5%")
        (field (name "MANUFACTURER") "YAGEO")
        (field (name "CREATED BY") "YTL")
      )
      (libsource (lib "*") (part "RESISTOR_Dup1"))
    )
    (comp (ref "R11")
      (value "30K")
      (footprint "R0402")
      (description "30K +/-5% 1/16W 0402 ROHS")
      (fields
        (field (name "TOLERANCE") "5%")
        (field (name "MANUFACTURER") "YAGEO")
        (field (name "CREATED BY") "YTL")
      )
      (libsource (lib "*") (part "RESISTOR_Dup1"))
    )
    (comp (ref "R12")
      (value "10K")
      (footprint "R0402")
      (description "10K +/-1% 1/16W 0402 ROHS")
      (fields
        (field (name "TOLERANCE") "5%")
        (field (name "MANUFACTURER") "YAGEO")
        (field (name "CREATED BY") "YTL")
      )
      (libsource (lib "*") (part "RESISTOR_Dup1"))
    )
    (comp (ref "R13")
      (value "30K")
      (footprint "R0402")
      (description "30K +/-5% 1/16W 0402 ROHS")
      (fields
        (field (name "TOLERANCE") "5%")
        (field (name "MANUFACTURER") "YAGEO")
        (field (name "CREATED BY") "YTL")
      )
      (libsource (lib "*") (part "RESISTOR_Dup1"))
    )
    (comp (ref "R14")
      (value "52.3K 1%")
      (footprint "R0402")
      (description "52.3K +/-1% 1/16W 0402 ROHS")
      (fields
        (field (name "TOLERANCE") "5%")
        (field (name "MANUFACTURER") "YAGEO")
        (field (name "CREATED BY") "YTL")
      )
      (libsource (lib "*") (part "RESISTOR_Dup1"))
    )
    (comp (ref "R15")
      (value "11.5K 1%")
      (footprint "R0402")
      (description "11.5K +/-1% 1/16W 0402 ROHS")
      (fields
        (field (name "TOLERANCE") "5%")
        (field (name "MANUFACTURER") "YAGEO")
        (field (name "CREATED BY") "YTL")
      )
      (libsource (lib "*") (part "RESISTOR_Dup1"))
    )
    (comp (ref "R16")
      (value "47K")
      (footprint "R0402")
      (description "47K +/-1% 1/16W 0402 ROHS")
      (fields
        (field (name "TOLERANCE") "5%")
        (field (name "MANUFACTURER") "YAGEO")
        (field (name "CREATED BY") "YTL")
      )
      (libsource (lib "*") (part "RESISTOR_Dup1"))
    )
    (comp (ref "R17")
      (value "10K")
      (footprint "R0402")
      (description "10K +/-1% 1/16W 0402 ROHS")
      (fields
        (field (name "TOLERANCE") "5%")
        (field (name "MANUFACTURER") "YAGEO")
        (field (name "CREATED BY") "YTL")
      )
      (libsource (lib "*") (part "RESISTOR_Dup1"))
    )
    (comp (ref "R18")
      (value "15K 1%")
      (footprint "R0402")
      (description "15K +/-1% 1/16W 0402 ROHS")
      (fields
        (field (name "TOLERANCE") "5%")
        (field (name "MANUFACTURER") "YAGEO")
        (field (name "CREATED BY") "YTL")
      )
      (libsource (lib "*") (part "RESISTOR_Dup1"))
    )
    (comp (ref "R19")
      (value "11.5K 1%")
      (footprint "R0402")
      (description "11.5K +/-1% 1/16W 0402 ROHS")
      (fields
        (field (name "TOLERANCE") "5%")
        (field (name "MANUFACTURER") "YAGEO")
        (field (name "CREATED BY") "YTL")
      )
      (libsource (lib "*") (part "RESISTOR_Dup1"))
    )
    (comp (ref "R20")
      (value "47K")
      (footprint "R0402")
      (description "47K +/-1% 1/16W 0402 ROHS")
      (fields
        (field (name "TOLERANCE") "5%")
        (field (name "MANUFACTURER") "YAGEO")
        (field (name "CREATED BY") "YTL")
      )
      (libsource (lib "*") (part "RESISTOR_Dup1"))
    )
    (comp (ref "R21")
      (value "10R 1%")
      (footprint "R0603")
      (description "10R +/-1% 1/10W 0603 ROHS")
      (fields
        (field (name "TOLERANCE") "5%")
        (field (name "MANUFACTURER") "YAGEO")
        (field (name "CREATED BY") "YTL")
      )
      (libsource (lib "*") (part "RESISTOR_Dup1"))
    )
    (comp (ref "R22")
      (value "2.2R")
      (footprint "R0402")
      (description "2.2R +/-5% 1/16W 0402 ROHS")
      (fields
        (field (name "TOLERANCE") "5%")
        (field (name "MANUFACTURER") "YAGEO")
        (field (name "CREATED BY") "YTL")
      )
      (libsource (lib "*") (part "RESISTOR_Dup1"))
    )
    (comp (ref "R23")
      (value "2.2R")
      (footprint "R0402")
      (description "2.2R +/-5% 1/16W 0402 ROHS")
      (fields
        (field (name "TOLERANCE") "5%")
        (field (name "MANUFACTURER") "YAGEO")
        (field (name "CREATED BY") "YTL")
      )
      (libsource (lib "*") (part "RESISTOR_Dup1"))
    )
    (comp (ref "R24")
      (value "NC/100R")
      (footprint "R0402")
      (description "100R +/-5% 1/16W 0402 ROHS")
      (fields
        (field (name "TOLERANCE") "5%")
        (field (name "MANUFACTURER") "YAGEO")
        (field (name "CREATED BY") "YTL")
      )
      (libsource (lib "*") (part "RESISTOR_Dup1"))
    )
    (comp (ref "R25")
      (value "NC/100R")
      (footprint "R0402")
      (description "100R +/-5% 1/16W 0402 ROHS")
      (fields
        (field (name "TOLERANCE") "5%")
        (field (name "MANUFACTURER") "YAGEO")
        (field (name "CREATED BY") "YTL")
      )
      (libsource (lib "*") (part "RESISTOR_Dup1"))
    )
    (comp (ref "R26")
      (value "2.2K")
      (footprint "R0402")
      (description "2.2K +/-1% 1/16W 0402 ROHS")
      (fields (field (name "PUBLISHER") "Altium Limited"))
      (libsource (lib "FL01M1V5") (part "RES2"))
    )
    (comp (ref "R27")
      (value "47K")
      (footprint "R0402")
      (description "47K +/-1% 1/16W 0402 ROHS")
      (libsource (lib "*") (part "RESISTOR_Dup2"))
    )
    (comp (ref "R28")
      (value "2.2K")
      (footprint "R0402")
      (description "2.2K +/-1% 1/16W 0402 ROHS")
      (fields (field (name "PUBLISHER") "Altium Limited"))
      (libsource (lib "FL01M1V5") (part "RES2"))
    )
    (comp (ref "R29")
      (value "10K")
      (footprint "R0402")
      (description "10K +/-1% 1/16W 0402 ROHS")
      (fields
        (field (name "TOLERANCE") "5%")
        (field (name "MANUFACTURER") "YAGEO")
        (field (name "CREATED BY") "YTL")
      )
      (libsource (lib "*") (part "RESISTOR_Dup1"))
    )
    (comp (ref "R31")
      (value "2.2K")
      (footprint "R0402")
      (description "2.2K +/-1% 1/16W 0402 ROHS")
      (fields
        (field (name "TOLERANCE") "5%")
        (field (name "MANUFACTURER") "YAGEO")
        (field (name "CREATED BY") "YTL")
      )
      (libsource (lib "*") (part "RESISTOR_Dup1"))
    )
    (comp (ref "R32")
      (value "2.2K")
      (footprint "R0402")
      (description "2.2K +/-1% 1/16W 0402 ROHS")
      (fields
        (field (name "TOLERANCE") "5%")
        (field (name "MANUFACTURER") "YAGEO")
        (field (name "CREATED BY") "YTL")
      )
      (libsource (lib "*") (part "RESISTOR_Dup1"))
    )
    (comp (ref "R34")
      (value "220R")
      (footprint "R0402")
      (description "220R +/-1% 1/16W 0402 ROHS")
      (fields
        (field (name "TOLERANCE") "5%")
        (field (name "MANUFACTURER") "YAGEO")
        (field (name "CREATED BY") "YTL")
      )
      (libsource (lib "*") (part "RESISTOR_Dup1"))
    )
    (comp (ref "R35")
      (value "4.3K")
      (footprint "R0402")
      (description "4.3K +/-1% 1/16W 0402 ROHS")
      (fields
        (field (name "TOLERANCE") "5%")
        (field (name "MANUFACTURER") "YAGEO")
        (field (name "CREATED BY") "YTL")
      )
      (libsource (lib "*") (part "RESISTOR_Dup1"))
    )
    (comp (ref "R36")
      (value "2K")
      (footprint "R0402")
      (description "2K +/-1% 1/16W 0402 ROHS")
      (fields
        (field (name "TOLERANCE") "5%")
        (field (name "MANUFACTURER") "YAGEO")
        (field (name "CREATED BY") "YTL")
      )
      (libsource (lib "*") (part "RESISTOR_Dup1"))
    )
    (comp (ref "R37")
      (value "330R")
      (footprint "R0402")
      (description "330R +/-5% 1/16W 0402 ROHS")
      (fields
        (field (name "TOLERANCE") "5%")
        (field (name "MANUFACTURER") "YAGEO")
        (field (name "CREATED BY") "YTL")
      )
      (libsource (lib "*") (part "RESISTOR_Dup1"))
    )
    (comp (ref "R38")
      (value "75R 1%")
      (footprint "R0402")
      (description "75R +/-1% 1/16W 0402 ROHS")
      (fields
        (field (name "TOLERANCE") "5%")
        (field (name "MANUFACTURER") "YAGEO")
        (field (name "CREATED BY") "YTL")
      )
      (libsource (lib "*") (part "RESISTOR_Dup1"))
    )
    (comp (ref "R39")
      (value "47K")
      (footprint "R0402")
      (description "47K +/-1% 1/16W 0402 ROHS")
      (fields
        (field (name "TOLERANCE") "5%")
        (field (name "MANUFACTURER") "YAGEO")
        (field (name "CREATED BY") "YTL")
      )
      (libsource (lib "*") (part "RESISTOR_Dup1"))
    )
    (comp (ref "R40")
      (value "10K")
      (footprint "R0402")
      (description "10K +/-1% 1/16W 0402 ROHS")
      (libsource (lib "LM") (part "RES"))
    )
    (comp (ref "RXD")
      (value "Test Point")
      (footprint "Test Point")
      (libsource (lib "VD_DES3V0") (part "Test Point"))
    )
    (comp (ref "SCL")
      (value "Test Point")
      (footprint "Test Point")
      (libsource (lib "VD_DES3V0") (part "Test Point"))
    )
    (comp (ref "SDA")
      (value "Test Point")
      (footprint "Test Point")
      (libsource (lib "VD_DES3V0") (part "Test Point"))
    )
    (comp (ref "TXD")
      (value "Test Point")
      (footprint "Test Point")
      (libsource (lib "VD_DES3V0") (part "Test Point"))
    )
    (comp (ref "U1")
      (value "F1C200s-QFN88")
      (footprint "QFN88 10*10MM")
      (libsource (lib "VD_MAIN3V0") (part "F1C200S"))
    )
    (comp (ref "U2")
      (value "ME6210A33PG (SOT89-3)")
      (footprint "SOT-89")
      (fields (field (name "ALTIUM_UNNAMED_1") "ME6210A33M3G"))
      (libsource (lib "LM") (part "HT7333"))
    )
    (comp (ref "U3")
      (value "N76E003AT20(TSSOP20)")
      (footprint "InMain1V0:SOP20")
      (description "IC")
      (fields (field (name "ALTIUM_UNNAMED_1") "N76E003AT20"))
      (libsource (lib "LM") (part "N76E003AT20"))
    )
    (comp (ref "U4") (value "W25Q128JVSIQ") (footprint "SOP8-208mil") (libsource (lib "LM") (part "25Q128")))
    (comp (ref "U5")
      (value "JW5052S")
      (footprint "TSOT23-6")
      (description "JW5052S(3.7V~18V/2A  Sync. Step-Down Converter)")
      (libsource (lib "ZhuhaiSch") (part "JW5052S"))
    )
    (comp (ref "U6")
      (value "NS4150")
      (footprint "SOIC8")
      (description "NS4150 (SOIC8)")
      (libsource (lib "LM") (part "HT6871"))
    )
    (comp (ref "U7")
      (value "BM8563ESA")
      (footprint "SOP8")
      (description "PCF8563T (SOP-8) OR BM8563ESA(SOP8)")
      (libsource (lib "FL2Main1v3") (part "PCF8563T"))
    )
    (comp (ref "U8")
      (value "JW5052S")
      (footprint "TSOT23-6")
      (description "JW5052S(3.7V~18V/2A  Sync. Step-Down Converter)")
      (libsource (lib "ZhuhaiSch") (part "JW5052S"))
    )
    (comp (ref "U9")
      (value "JW5052S")
      (footprint "TSOT23-6")
      (description "JW5052S(3.7V~18V/2A  Sync. Step-Down Converter)")
      (libsource (lib "ZhuhaiSch") (part "JW5052S"))
    )
    (comp (ref "U10")
      (value "AP3032KTR-G1")
      (footprint "SOT-23-6")
      (description "AP3032KTR-G1  (SOT-23-6)")
      (libsource (lib "*") (part "AP3031_0"))
    )
    (comp (ref "U11")
      (value "RT9193-33GB")
      (footprint "SOT-23-5")
      (description "RT9193-33GB (SOT23-5)")
      (libsource (lib "Face4Main1V6") (part "RT9193-33GB"))
    )
    (comp (ref "U12")
      (value "ME6211A28M3G-N")
      (footprint "SOT-23-3")
      (description "ME6211A12M3G-N (SOT-23-3)")
      (libsource (lib "FL01M1V5") (part "Voltage_Regulator"))
    )
    (comp (ref "X1")
      (value "32.768KHz-12.5pF-20PPM")
      (footprint "SMD-7015_4P")
      (description "贴片无源晶振/SSP-T7-F 32.768kHz 20PPM 12.5p 编带")
      (libsource (lib "S10_5V1") (part "XTAL"))
    )
    (comp (ref "X2")
      (value "24MHz-12pF-10PPM")
      (footprint "CRY-3225")
      (description "贴片无源晶振/YSX321SL 24MHZ 10PF 10PPM -40~+85 袋装")
      (fields (field (name "PART NUMBER") "7M24000004"))
      (libsource (lib "FL01M1V5") (part "CRYSTAL-4_0"))
    )
  )
  (nets
    (net (code "1") (name "/1V1_SW") (class "Default")
      (node (ref "C31") (pin "2") (pinfunction "2_2") (pintype "passive"))
      (node (ref "L2") (pin "1") (pinfunction "1_1") (pintype "passive"))
      (node (ref "U9") (pin "6") (pinfunction "SW_6") (pintype "passive"))
    )
    (net (code "2") (name "/2V5_SW") (class "Default")
      (node (ref "C44") (pin "1") (pinfunction "1_1") (pintype "passive"))
      (node (ref "L3") (pin "1") (pinfunction "1_1") (pintype "passive"))
      (node (ref "U8") (pin "6") (pinfunction "SW_6") (pintype "passive"))
    )
    (net (code "3") (name "/3V3_SW") (class "Default")
      (node (ref "C27") (pin "1") (pinfunction "1_1") (pintype "passive"))
      (node (ref "L1") (pin "1") (pinfunction "1_1") (pintype "passive"))
      (node (ref "U5") (pin "6") (pinfunction "SW_6") (pintype "passive"))
    )
    (net (code "4") (name "/CVBS") (class "Default")
      (node (ref "C67") (pin "2") (pinfunction "2_2") (pintype "passive"))
      (node (ref "CN4") (pin "2") (pinfunction "2_2") (pintype "passive"))
      (node (ref "E15") (pin "1") (pinfunction "1_1") (pintype "passive"))
      (node (ref "R38") (pin "1") (pinfunction "1_1") (pintype "passive"))
    )
    (net (code "5") (name "/DISP") (class "Default")
      (node (ref "CN9") (pin "7") (pinfunction "DISP_7") (pintype "passive+no_connect"))
    )
    (net (code "6") (name "/Debug_RX") (class "Default")
      (node (ref "CN6") (pin "1") (pinfunction "1_1") (pintype "passive"))
      (node (ref "E11") (pin "1") (pinfunction "1_1") (pintype "passive"))
      (node (ref "R25") (pin "2") (pinfunction "2_2") (pintype "passive"))
    )
    (net (code "7") (name "/Debug_TX") (class "Default")
      (node (ref "CN6") (pin "2") (pinfunction "2_2") (pintype "passive"))
      (node (ref "E12") (pin "1") (pinfunction "1_1") (pintype "passive"))
      (node (ref "R24") (pin "2") (pinfunction "2_2") (pintype "passive"))
    )
    (net (code "8") (name "/HOLD") (class "Default")
      (node (ref "R6") (pin "1") (pinfunction "1_1") (pintype "passive"))
      (node (ref "U4") (pin "7") (pinfunction "HOLD#_7") (pintype "passive"))
    )
    (net (code "9") (name "/HPCOM") (class "Default")
      (node (ref "C57") (pin "2") (pinfunction "2_2") (pintype "passive"))
      (node (ref "U1") (pin "2") (pinfunction "HPCOM_FB_2") (pintype "passive"))
      (node (ref "U1") (pin "3") (pinfunction "HPCOM_3") (pintype "passive"))
    )
    (net (code "10") (name "/HPR") (class "Default")
      (node (ref "C12") (pin "2") (pinfunction "2_2") (pintype "passive"))
      (node (ref "U1") (pin "88") (pinfunction "HPR_88") (pintype "passive"))
    )
    (net (code "11") (name "/ICPCK") (class "Default")
      (node (ref "CN3") (pin "2") (pinfunction "2_2") (pintype "passive"))
      (node (ref "E5") (pin "1") (pinfunction "1_1") (pintype "passive"))
      (node (ref "U3") (pin "18") (pinfunction "P0.2/ICPCK/OCDCK/RXD_1/[SCL]_18") (pintype "passive"))
    )
    (net (code "12") (name "/ICPDA") (class "Default")
      (node (ref "CN3") (pin "1") (pinfunction "1_1") (pintype "passive"))
      (node (ref "E4") (pin "1") (pinfunction "1_1") (pintype "passive"))
      (node (ref "U3") (pin "8") (pinfunction "P1.6/OCDDA/ICPDA/TXD_1/[SDA]_8") (pintype "passive"))
    )
    (net (code "13") (name "/LCD_BL_EN") (class "Default")
      (node (ref "R27") (pin "1") (pinfunction "1_1") (pintype "passive"))
      (node (ref "U1") (pin "45") (pinfunction "CSI_D1_/_PE4_45") (pintype "passive"))
    )
    (net (code "14") (name "/LCD_CLK") (class "Default")
      (node (ref "CN9") (pin "38") (pinfunction "DCLK_38") (pintype "passive"))
      (node (ref "U1") (pin "26") (pinfunction "LCD_CLK_/_PD18_26") (pintype "passive"))
    )
    (net (code "15") (name "/LCD_D2") (class "Default")
      (node (ref "CN9") (pin "14") (pinfunction "B2_14") (pintype "passive"))
      (node (ref "U1") (pin "6") (pinfunction "LCD_D2/PD0_6") (pintype "passive"))
    )
    (net (code "16") (name "/LCD_D3") (class "Default")
      (node (ref "CN9") (pin "15") (pinfunction "B3_15") (pintype "passive"))
      (node (ref "U1") (pin "7") (pinfunction "LCD_D3/PD1_7") (pintype "passive"))
    )
    (net (code "17") (name "/LCD_D4") (class "Default")
      (node (ref "CN9") (pin "16") (pinfunction "B4_16") (pintype "passive"))
      (node (ref "U1") (pin "8") (pinfunction "LCD_D4/PD2_8") (pintype "passive"))
    )
    (net (code "18") (name "/LCD_D5") (class "Default")
      (node (ref "CN9") (pin "17") (pinfunction "B5_17") (pintype "passive"))
      (node (ref "U1") (pin "9") (pinfunction "LCD_D5/PD3_9") (pintype "passive"))
    )
    (net (code "19") (name "/LCD_D6") (class "Default")
      (node (ref "CN9") (pin "18") (pinfunction "B6_18") (pintype "passive"))
      (node (ref "U1") (pin "10") (pinfunction "LCD_D6/PD4_10") (pintype "passive"))
    )
    (net (code "20") (name "/LCD_D7") (class "Default")
      (node (ref "CN9") (pin "19") (pinfunction "B7_19") (pintype "passive"))
      (node (ref "U1") (pin "11") (pinfunction "LCD_D7/PD5_11") (pintype "passive"))
    )
    (net (code "21") (name "/LCD_D10") (class "Default")
      (node (ref "CN9") (pin "22") (pinfunction "G2_22") (pintype "passive"))
      (node (ref "U1") (pin "12") (pinfunction "LCD_D10/PD6_12") (pintype "passive"))
    )
    (net (code "22") (name "/LCD_D11") (class "Default")
      (node (ref "CN9") (pin "23") (pinfunction "G3_23") (pintype "passive"))
      (node (ref "U1") (pin "13") (pinfunction "LCD_D11/PD7_13") (pintype "passive"))
    )
    (net (code "23") (name "/LCD_D12") (class "Default")
      (node (ref "CN9") (pin "24") (pinfunction "G4_24") (pintype "passive"))
      (node (ref "U1") (pin "14") (pinfunction "LCD_D12/PD8_14") (pintype "passive"))
    )
    (net (code "24") (name "/LCD_D13") (class "Default")
      (node (ref "CN9") (pin "25") (pinfunction "G5_25") (pintype "passive"))
      (node (ref "U1") (pin "15") (pinfunction "LCD_D13/PD9_15") (pintype "passive"))
    )
    (net (code "25") (name "/LCD_D14") (class "Default")
      (node (ref "CN9") (pin "26") (pinfunction "G6_26") (pintype "passive"))
      (node (ref "U1") (pin "16") (pinfunction "LCD_D14/PD10_16") (pintype "passive"))
    )
    (net (code "26") (name "/LCD_D15") (class "Default")
      (node (ref "CN9") (pin "27") (pinfunction "G7_27") (pintype "passive"))
      (node (ref "U1") (pin "17") (pinfunction "LCD_D15/PD11_17") (pintype "passive"))
    )
    (net (code "27") (name "/LCD_D18") (class "Default")
      (node (ref "CN9") (pin "30") (pinfunction "R2_30") (pintype "passive"))
      (node (ref "U1") (pin "18") (pinfunction "LCD_D18/PD12_18") (pintype "passive"))
    )
    (net (code "28") (name "/LCD_D19") (class "Default")
      (node (ref "CN9") (pin "31") (pinfunction "R3_31") (pintype "passive"))
      (node (ref "U1") (pin "19") (pinfunction "LCD_D19/PD13_19") (pintype "passive"))
    )
    (net (code "29") (name "/LCD_D20") (class "Default")
      (node (ref "CN9") (pin "32") (pinfunction "R4_32") (pintype "passive"))
      (node (ref "U1") (pin "21") (pinfunction "LCD_D20/PD14_21") (pintype "passive"))
    )
    (net (code "30") (name "/LCD_D21") (class "Default")
      (node (ref "CN9") (pin "33") (pinfunction "R5_33") (pintype "passive"))
      (node (ref "U1") (pin "23") (pinfunction "LCD_D21_/_PD15_23") (pintype "passive"))
    )
    (net (code "31") (name "/LCD_D22") (class "Default")
      (node (ref "CN9") (pin "34") (pinfunction "R6_34") (pintype "passive"))
      (node (ref "U1") (pin "24") (pinfunction "LCD_D22_/_PD16_24") (pintype "passive"))
    )
    (net (code "32") (name "/LCD_D23") (class "Default")
      (node (ref "CN9") (pin "35") (pinfunction "R7_35") (pintype "passive"))
      (node (ref "U1") (pin "25") (pinfunction "LCD_D23_/_PD17_25") (pintype "passive"))
    )
    (net (code "33") (name "/LCD_DE") (class "Default")
      (node (ref "CN9") (pin "52") (pinfunction "DE_52") (pintype "passive"))
      (node (ref "U1") (pin "27") (pinfunction "LCD_DE_/_PD19_27") (pintype "passive"))
    )
    (net (code "34") (name "/LCD_HSYNC") (class "Default")
      (node (ref "CN9") (pin "36") (pinfunction "HSYNC_36") (pintype "passive"))
      (node (ref "U1") (pin "28") (pinfunction "LCD_HSYNC_/_PD20_28") (pintype "passive"))
    )
    (net (code "35") (name "/LCD_RST") (class "Default")
      (node (ref "CN9") (pin "8") (pinfunction "RESET_8") (pintype "passive"))
      (node (ref "R29") (pin "1") (pinfunction "1_1") (pintype "passive"))
      (node (ref "U1") (pin "46") (pinfunction "CSI_D0_/_PE3_46") (pintype "passive"))
    )
    (net (code "36") (name "/LCD_VSYNC") (class "Default")
      (node (ref "CN9") (pin "37") (pinfunction "VSYNC_37") (pintype "passive"))
      (node (ref "U1") (pin "29") (pinfunction "LCD_VSYNC_/_PD21_29") (pintype "passive"))
    )
    (net (code "37") (name "/LED+") (class "Default")
      (node (ref "C39") (pin "2") (pinfunction "2_2") (pintype "passive"))
      (node (ref "CN9") (pin "3") (pinfunction "LED+_3") (pintype "passive"))
      (node (ref "CN9") (pin "4") (pinfunction "LED+_4") (pintype "passive"))
      (node (ref "D3") (pin "2") (pinfunction "2_2") (pintype "passive"))
      (node (ref "U10") (pin "5") (pinfunction "OVP_5") (pintype "passive"))
    )
    (net (code "38") (name "/LED-") (class "Default")
      (node (ref "CN9") (pin "1") (pinfunction "LED-_1") (pintype "passive"))
      (node (ref "CN9") (pin "2") (pinfunction "LED-_2") (pintype "passive"))
      (node (ref "R21") (pin "1") (pinfunction "1_1") (pintype "passive"))
      (node (ref "U10") (pin "3") (pinfunction "FB_3") (pintype "passive"))
    )
    (net (code "39") (name "/LS+") (class "Default")
      (node (ref "CN5") (pin "1") (pinfunction "1_1") (pintype "passive"))
      (node (ref "E1") (pin "1") (pinfunction "1_1") (pintype "passive"))
      (node (ref "U6") (pin "5") (pinfunction "OUT+_5") (pintype "passive"))
    )
    (net (code "40") (name "/LS-") (class "Default")
      (node (ref "CN5") (pin "2") (pinfunction "2_2") (pintype "passive"))
      (node (ref "E2") (pin "1") (pinfunction "1_1") (pintype "passive"))
      (node (ref "U6") (pin "8") (pinfunction "OUT-_8") (pintype "passive"))
    )
    (net (code "41") (name "/LX_LCD") (class "Default")
      (node (ref "D3") (pin "1") (pinfunction "1_1") (pintype "passive"))
      (node (ref "L4") (pin "2") (pinfunction "2_2") (pintype "passive"))
      (node (ref "U10") (pin "1") (pinfunction "LX_1") (pintype "passive"))
    )
    (net (code "42") (name "/Lock") (class "Default")
      (node (ref "CN7") (pin "2") (pinfunction "2_2") (pintype "passive"))
      (node (ref "D6") (pin "2") (pinfunction "K_2") (pintype "output"))
    )
    (net (code "43") (name "/Lock_IN") (class "Default")
      (node (ref "D6") (pin "1") (pinfunction "A_1") (pintype "input"))
      (node (ref "U3") (pin "10") (pinfunction "P1.5/~{SS}/IC7/PWM5_10") (pintype "passive"))
    )
    (net (code "44") (name "/MBIAS") (class "Default")
      (node (ref "C60") (pin "1") (pinfunction "1_1") (pintype "passive"))
      (node (ref "R35") (pin "1") (pinfunction "1_1") (pintype "passive"))
      (node (ref "R36") (pin "1") (pinfunction "1_1") (pintype "passive"))
    )
    (net (code "45") (name "/MCU_INT") (class "Default")
      (node (ref "D9") (pin "2") (pinfunction "K_2") (pintype "output"))
      (node (ref "MCU_INT") (pin "1") (pinfunction "50_1") (pintype "passive"))
      (node (ref "U3") (pin "1") (pinfunction "P0.5/AIN4/T0/IC6/PWM2_1") (pintype "passive"))
    )
    (net (code "46") (name "/MICI") (class "Default")
      (node (ref "CN4") (pin "4") (pinfunction "4_4") (pintype "passive"))
      (node (ref "E16") (pin "1") (pinfunction "1_1") (pintype "passive"))
      (node (ref "R34") (pin "2") (pinfunction "2_2") (pintype "passive"))
      (node (ref "R35") (pin "2") (pinfunction "2_2") (pintype "passive"))
    )
    (net (code "47") (name "/MICIN") (class "Default")
      (node (ref "C59") (pin "1") (pinfunction "1_1") (pintype "passive"))
      (node (ref "U1") (pin "87") (pinfunction "MICIN_87") (pintype "passive"))
    )
    (net (code "48") (name "/NRST") (class "Default")
      (node (ref "C49") (pin "1") (pinfunction "1_1") (pintype "passive"))
      (node (ref "CN3") (pin "4") (pinfunction "4_4") (pintype "passive"))
      (node (ref "E6") (pin "1") (pinfunction "1_1") (pintype "passive"))
      (node (ref "U3") (pin "4") (pinfunction "P2.0/~{RST}_4") (pintype "passive"))
    )
    (net (code "49") (name "/PWR-EN") (class "Default")
      (node (ref "D8") (pin "2") (pinfunction "2A_2") (pintype "passive"))
      (node (ref "U3") (pin "20") (pinfunction "P0.4/AIN5/STADC/PWM3/IC3_20") (pintype "passive"))
    )
    (net (code "50") (name "/PWRON") (class "Default")
      (node (ref "D8") (pin "3") (pinfunction "K_3") (pintype "passive"))
      (node (ref "R1") (pin "1") (pinfunction "1_1") (pintype "passive"))
      (node (ref "U5") (pin "4") (pinfunction "EN_4") (pintype "passive"))
      (node (ref "U8") (pin "4") (pinfunction "EN_4") (pintype "passive"))
      (node (ref "U9") (pin "4") (pinfunction "EN_4") (pintype "passive"))
    )
    (net (code "51") (name "/Power") (class "Default")
      (node (ref "CN7") (pin "4") (pinfunction "4_4") (pintype "passive"))
      (node (ref "D7") (pin "2") (pinfunction "K_2") (pintype "output"))
    )
    (net (code "52") (name "/Power_IN") (class "Default")
      (node (ref "D7") (pin "1") (pinfunction "A_1") (pintype "input"))
      (node (ref "U3") (pin "6") (pinfunction "P1.7/AIN0/~{INT1}_6") (pintype "passive"))
    )
    (net (code "53") (name "/RESET") (class "Default")
      (node (ref "C37") (pin "2") (pinfunction "2_2") (pintype "passive"))
      (node (ref "R8") (pin "2") (pinfunction "2_2") (pintype "passive"))
      (node (ref "U1") (pin "70") (pinfunction "RESET_70") (pintype "passive"))
    )
    (net (code "54") (name "/RXD") (class "Default")
      (node (ref "CN4") (pin "8") (pinfunction "8_8") (pintype "passive"))
      (node (ref "E14") (pin "1") (pinfunction "1_1") (pintype "passive"))
      (node (ref "RXD") (pin "1") (pinfunction "50_1") (pintype "passive"))
      (node (ref "U3") (pin "3") (pinfunction "P0.7/AIN2/RXD_3") (pintype "passive"))
    )
    (net (code "55") (name "/SCL") (class "Default")
      (node (ref "R31") (pin "1") (pinfunction "1_1") (pintype "passive"))
      (node (ref "SCL") (pin "1") (pinfunction "50_1") (pintype "passive"))
      (node (ref "U1") (pin "37") (pinfunction "DA_MCLK_/_PE12_37") (pintype "passive"))
      (node (ref "U3") (pin "12") (pinfunction "P1.3/SCL/[STADC]_12") (pintype "passive"))
      (node (ref "U7") (pin "6") (pinfunction "SCL_6") (pintype "passive"))
    )
    (net (code "56") (name "/SD0_CLK") (class "Default")
      (node (ref "U1") (pin "56") (pinfunction "SDC0_CLK_/_PF2_56") (pintype "passive+no_connect"))
    )
    (net (code "57") (name "/SD0_CMD") (class "Default")
      (node (ref "U1") (pin "55") (pinfunction "SDC0_CMD_/_PF3_55") (pintype "passive+no_connect"))
    )
    (net (code "58") (name "/SD0_DATA0") (class "Default")
      (node (ref "U1") (pin "57") (pinfunction "SDC0_D0_/_PF1_57") (pintype "passive+no_connect"))
    )
    (net (code "59") (name "/SD0_DATA1") (class "Default")
      (node (ref "U1") (pin "58") (pinfunction "SDC0_D1_/_PF0_58") (pintype "passive+no_connect"))
    )
    (net (code "60") (name "/SD0_DATA2") (class "Default")
      (node (ref "U1") (pin "53") (pinfunction "SDC0_D2_/_PF5_53") (pintype "passive+no_connect"))
    )
    (net (code "61") (name "/SD0_DATA3") (class "Default")
      (node (ref "U1") (pin "54") (pinfunction "SDC0_D3_/_PF4_54") (pintype "passive+no_connect"))
    )
    (net (code "62") (name "/SDA") (class "Default")
      (node (ref "R32") (pin "1") (pinfunction "1_1") (pintype "passive"))
      (node (ref "SDA") (pin "1") (pinfunction "50_1") (pintype "passive"))
      (node (ref "U1") (pin "38") (pinfunction "CLK_OUT_/_PE11_38") (pintype "passive"))
      (node (ref "U3") (pin "11") (pinfunction "P1.4/SDA/FB/PWM1_11") (pintype "passive"))
      (node (ref "U7") (pin "5") (pinfunction "SDA_5") (pintype "passive"))
    )
    (net (code "63") (name "/SPI0-CLK") (class "Default")
      (node (ref "R7") (pin "1") (pinfunction "1_1") (pintype "passive"))
      (node (ref "U1") (pin "59") (pinfunction "SPI0_CLK_/_PC0_59") (pintype "passive"))
      (node (ref "U4") (pin "6") (pinfunction "CLK_6") (pintype "passive"))
    )
    (net (code "64") (name "/SPI0-CS") (class "Default")
      (node (ref "U1") (pin "60") (pinfunction "SPI0_CS_/_PC1_60") (pintype "passive"))
      (node (ref "U4") (pin "1") (pinfunction "CS#_1") (pintype "passive"))
    )
    (net (code "65") (name "/SPI0-MISO") (class "Default")
      (node (ref "D4") (pin "1") (pinfunction "A_1") (pintype "input"))
      (node (ref "R39") (pin "1") (pinfunction "1_1") (pintype "passive"))
      (node (ref "R9") (pin "1") (pinfunction "1_1") (pintype "passive"))
      (node (ref "U1") (pin "61") (pinfunction "SPI0_MISO_/_PC2_61") (pintype "passive"))
      (node (ref "U4") (pin "2") (pinfunction "MISO_2") (pintype "passive"))
    )
    (net (code "66") (name "/SPI0-MOSI") (class "Default")
      (node (ref "R5") (pin "1") (pinfunction "1_1") (pintype "passive"))
      (node (ref "U1") (pin "62") (pinfunction "SPI0_MOSI_/_PC3_62") (pintype "passive"))
      (node (ref "U4") (pin "5") (pinfunction "MOSI_5") (pintype "passive"))
    )
    (net (code "67") (name "/SPI0-WP") (class "Default")
      (node (ref "R10") (pin "1") (pinfunction "1_1") (pintype "passive"))
      (node (ref "U4") (pin "3") (pinfunction "WP#_3") (pintype "passive"))
    )
    (net (code "68") (name "/SPI1-CLK") (class "Default")
      (node (ref "U1") (pin "64") (pinfunction "TP_Y1_/_PA2_64") (pintype "passive+no_connect"))
    )
    (net (code "69") (name "/SPI1-CS") (class "Default")
      (node (ref "U1") (pin "66") (pinfunction "TP_X1_/_PA0_66") (pintype "passive+no_connect"))
    )
    (net (code "70") (name "/SPI1-MISO") (class "Default")
      (node (ref "U1") (pin "63") (pinfunction "TP_Y2_/_PA3_63") (pintype "passive+no_connect"))
    )
    (net (code "71") (name "/SPI1-MOSI") (class "Default")
      (node (ref "U1") (pin "65") (pinfunction "TP_X2_/_PA1_65") (pintype "passive+no_connect"))
    )
    (net (code "72") (name "/SPK_EN") (class "Default")
      (node (ref "R12") (pin "1") (pinfunction "1_1") (pintype "passive"))
      (node (ref "U1") (pin "44") (pinfunction "CSI_D2_/_PE5_44") (pintype "passive"))
      (node (ref "U6") (pin "1") (pinfunction "CTRL_1") (pintype "passive"))
    )
    (net (code "73") (name "/TVIN") (class "Default")
      (node (ref "C69") (pin "1") (pinfunction "1_1") (pintype "passive"))
      (node (ref "L5") (pin "2") (pinfunction "2_2") (pintype "passive"))
      (node (ref "U1") (pin "78") (pinfunction "TVIN0_78") (pintype "passive"))
    )
    (net (code "74") (name "/TXD") (class "Default")
      (node (ref "CN4") (pin "6") (pinfunction "6_6") (pintype "passive"))
      (node (ref "E13") (pin "1") (pinfunction "1_1") (pintype "passive"))
      (node (ref "TXD") (pin "1") (pinfunction "50_1") (pintype "passive"))
      (node (ref "U3") (pin "2") (pinfunction "P0.6/AIN3/TXD_2") (pintype "passive"))
    )
    (net (code "75") (name "/UART0_RX") (class "Default")
      (node (ref "R25") (pin "1") (pinfunction "1_1") (pintype "passive"))
      (node (ref "U1") (pin "49") (pinfunction "CSI_HSYNC_/_PE0_49") (pintype "passive"))
    )
    (net (code "76") (name "/UART0_TX") (class "Default")
      (node (ref "R24") (pin "1") (pinfunction "1_1") (pintype "passive"))
      (node (ref "U1") (pin "48") (pinfunction "CSI_VSYNC_/_PE1_48") (pintype "passive"))
    )
    (net (code "77") (name "/USB_N") (class "Default")
      (node (ref "R23") (pin "1") (pinfunction "1_1") (pintype "passive"))
      (node (ref "U1") (pin "68") (pinfunction "DM_68") (pintype "passive"))
    )
    (net (code "78") (name "/USB_P") (class "Default")
      (node (ref "R22") (pin "1") (pinfunction "1_1") (pintype "passive"))
      (node (ref "U1") (pin "69") (pinfunction "DP_69") (pintype "passive"))
    )
    (net (code "79") (name "/U_N") (class "Default")
      (node (ref "CN8") (pin "2") (pinfunction "2_2") (pintype "passive"))
      (node (ref "E9") (pin "1") (pinfunction "1_1") (pintype "passive"))
      (node (ref "R23") (pin "2") (pinfunction "2_2") (pintype "passive"))
    )
    (net (code "80") (name "/U_P") (class "Default")
      (node (ref "CN8") (pin "3") (pinfunction "3_3") (pintype "passive"))
      (node (ref "E7") (pin "1") (pinfunction "1_1") (pintype "passive"))
      (node (ref "R22") (pin "2") (pinfunction "2_2") (pintype "passive"))
    )
    (net (code "81") (name "/VRA1") (class "Default")
      (node (ref "C54") (pin "2") (pinfunction "2_2") (pintype "passive"))
      (node (ref "U1") (pin "81") (pinfunction "VRA1_81") (pintype "passive"))
    )
    (net (code "82") (name "/VRA2") (class "Default")
      (node (ref "C55") (pin "2") (pinfunction "2_2") (pintype "passive"))
      (node (ref "R2") (pin "2") (pinfunction "2_2") (pintype "passive"))
      (node (ref "U1") (pin "83") (pinfunction "VRA2_83") (pintype "passive"))
    )
    (net (code "83") (name "/VRN") (class "Default")
      (node (ref "C64") (pin "2") (pinfunction "2_2") (pintype "passive"))
      (node (ref "C65") (pin "2") (pinfunction "2_2") (pintype "passive"))
      (node (ref "U1") (pin "75") (pinfunction "TV_VRN_75") (pintype "passive"))
    )
    (net (code "84") (name "/VRP") (class "Default")
      (node (ref "C65") (pin "1") (pinfunction "1_1") (pintype "passive"))
      (node (ref "C66") (pin "2") (pinfunction "2_2") (pintype "passive"))
      (node (ref "U1") (pin "76") (pinfunction "TV_VRP_76") (pintype "passive"))
    )
    (net (code "85") (name "/Voice") (class "Default")
      (node (ref "CN7") (pin "1") (pinfunction "1_1") (pintype "passive"))
      (node (ref "D5") (pin "2") (pinfunction "K_2") (pintype "output"))
    )
    (net (code "86") (name "/Voice_IN") (class "Default")
      (node (ref "D5") (pin "1") (pinfunction "A_1") (pintype "input"))
      (node (ref "U3") (pin "15") (pinfunction "P1.0/PWM2/IC2/SPCLK_15") (pintype "passive"))
    )
    (net (code "87") (name "/X24MI") (class "Default")
      (node (ref "C36") (pin "2") (pinfunction "2_2") (pintype "passive"))
      (node (ref "U1") (pin "51") (pinfunction "HOSCI_51") (pintype "passive"))
      (node (ref "X2") (pin "1") (pinfunction "XIN_1") (pintype "passive"))
    )
    (net (code "88") (name "/X24MO") (class "Default")
      (node (ref "C35") (pin "1") (pinfunction "1_1") (pintype "passive"))
      (node (ref "U1") (pin "52") (pinfunction "HOSCO_52") (pintype "passive"))
      (node (ref "X2") (pin "3") (pinfunction "XOUT_3") (pintype "passive"))
    )
    (net (code "89") (name "/XL") (class "Default")
      (node (ref "CN9") (pin "44") (pinfunction "XL_44") (pintype "passive+no_connect"))
    )
    (net (code "90") (name "/XR") (class "Default")
      (node (ref "CN9") (pin "6") (pinfunction "XR_6") (pintype "passive+no_connect"))
    )
    (net (code "91") (name "/YD") (class "Default")
      (node (ref "CN9") (pin "43") (pinfunction "YD_43") (pintype "passive+no_connect"))
    )
    (net (code "92") (name "/YU") (class "Default")
      (node (ref "CN9") (pin "5") (pinfunction "YU_5") (pintype "passive+no_connect"))
    )
    (net (code "93") (name "AGND") (class "Default")
      (node (ref "FB5") (pin "2") (pinfunction "2_2") (pintype "passive"))
      (node (ref "U1") (pin "82") (pinfunction "AGND_82") (pintype "passive"))
    )
    (net (code "94") (name "AVCC") (class "Default")
      (node (ref "C10") (pin "1") (pinfunction "1_1") (pintype "passive"))
      (node (ref "C9") (pin "2") (pinfunction "2_2") (pintype "passive"))
      (node (ref "FB1") (pin "1") (pinfunction "1_1") (pintype "passive"))
      (node (ref "R36") (pin "2") (pinfunction "2_2") (pintype "passive"))
      (node (ref "U1") (pin "80") (pinfunction "AVCC_80") (pintype "passive"))
    )
    (net (code "95") (name "DRAM-REF-AP") (class "Default")
      (node (ref "C1") (pin "1") (pinfunction "1_1") (pintype "passive"))
      (node (ref "C5") (pin "2") (pinfunction "2_2") (pintype "passive"))
      (node (ref "C6") (pin "2") (pinfunction "2_2") (pintype "passive"))
      (node (ref "C7") (pin "2") (pinfunction "2_2") (pintype "passive"))
      (node (ref "R26") (pin "1") (pinfunction "1_1") (pintype "passive"))
      (node (ref "R28") (pin "2") (pinfunction "2_2") (pintype "passive"))
      (node (ref "U1") (pin "33") (pinfunction "DRAM-VREF_/_PB3_33") (pintype "passive"))
    )
    (net (code "96") (name "GND") (class "Default")
      (node (ref "C10") (pin "2") (pinfunction "2_2") (pintype "passive"))
      (node (ref "C11") (pin "2") (pinfunction "2_2") (pintype "passive"))
      (node (ref "C13") (pin "2") (pinfunction "2_2") (pintype "passive"))
      (node (ref "C14") (pin "1") (pinfunction "1_1") (pintype "passive"))
      (node (ref "C15") (pin "2") (pinfunction "2_2") (pintype "passive"))
      (node (ref "C16") (pin "2") (pinfunction "2_2") (pintype "passive"))
      (node (ref "C17") (pin "1") (pinfunction "1_1") (pintype "passive"))
      (node (ref "C18") (pin "1") (pinfunction "1_1") (pintype "passive"))
      (node (ref "C19") (pin "1") (pinfunction "1_1") (pintype "passive"))
      (node (ref "C2") (pin "2") (pinfunction "2_2") (pintype "passive"))
      (node (ref "C20") (pin "1") (pinfunction "1_1") (pintype "passive"))
      (node (ref "C21") (pin "2") (pinfunction "2_2") (pintype "passive"))
      (node (ref "C22") (pin "1") (pinfunction "1_1") (pintype "passive"))
      (node (ref "C23") (pin "1") (pinfunction "1_1") (pintype "passive"))
      (node (ref "C24") (pin "1") (pinfunction "1_1") (pintype "passive"))
      (node (ref "C25") (pin "1") (pinfunction "1_1") (pintype "passive"))
      (node (ref "C26") (pin "1") (pinfunction "1_1") (pintype "passive"))
      (node (ref "C28") (pin "2") (pinfunction "2_2") (pintype "passive"))
      (node (ref "C29") (pin "1") (pinfunction "1_1") (pintype "passive"))
      (node (ref "C3") (pin "1") (pinfunction "1_1") (pintype "passive"))
      (node (ref "C30") (pin "1") (pinfunction "1_1") (pintype "passive"))
      (node (ref "C32") (pin "1") (pinfunction "1_1") (pintype "passive"))
      (node (ref "C33") (pin "2") (pinfunction "2_2") (pintype "passive"))
      (node (ref "C34") (pin "1") (pinfunction "1_1") (pintype "passive"))
      (node (ref "C35") (pin "2") (pinfunction "2_2") (pintype "passive"))
      (node (ref "C36") (pin "1") (pinfunction "1_1") (pintype "passive"))
      (node (ref "C37") (pin "1") (pinfunction "1_1") (pintype "passive"))
      (node (ref "C38") (pin "1") (pinfunction "1_1") (pintype "passive"))
      (node (ref "C39") (pin "1") (pinfunction "1_1") (pintype "passive"))
      (node (ref "C4") (pin "1") (pinfunction "1_1") (pintype "passive"))
      (node (ref "C40") (pin "2") (pinfunction "2_2") (pintype "passive"))
      (node (ref "C41") (pin "2") (pinfunction "2_2") (pintype "passive"))
      (node (ref "C42") (pin "2") (pinfunction "2_2") (pintype "passive"))
      (node (ref "C43") (pin "1") (pinfunction "1_1") (pintype "passive"))
      (node (ref "C45") (pin "2") (pinfunction "2_2") (pintype "passive"))
      (node (ref "C46") (pin "1") (pinfunction "1_1") (pintype "passive"))
      (node (ref "C47") (pin "1") (pinfunction "1_1") (pintype "passive"))
      (node (ref "C48") (pin "1") (pinfunction "1_1") (pintype "passive"))
      (node (ref "C49") (pin "2") (pinfunction "2_2") (pintype "passive"))
      (node (ref "C5") (pin "1") (pinfunction "1_1") (pintype "passive"))
      (node (ref "C50") (pin "1") (pinfunction "1_1") (pintype "passive"))
      (node (ref "C51") (pin "2") (pinfunction "2_2") (pintype "passive"))
      (node (ref "C52") (pin "2") (pinfunction "2_2") (pintype "passive"))
      (node (ref "C53") (pin "2") (pinfunction "2_2") (pintype "passive"))
      (node (ref "C54") (pin "1") (pinfunction "1_1") (pintype "passive"))
      (node (ref "C55") (pin "1") (pinfunction "1_1") (pintype "passive"))
      (node (ref "C56") (pin "1") (pinfunction "1_1") (pintype "passive"))
      (node (ref "C58") (pin "2") (pinfunction "2_2") (pintype "passive"))
      (node (ref "C6") (pin "1") (pinfunction "1_1") (pintype "passive"))
      (node (ref "C60") (pin "2") (pinfunction "2_2") (pintype "passive"))
      (node (ref "C61") (pin "2") (pinfunction "2_2") (pintype "passive"))
      (node (ref "C62") (pin "2") (pinfunction "2_2") (pintype "passive"))
      (node (ref "C64") (pin "1") (pinfunction "1_1") (pintype "passive"))
      (node (ref "C66") (pin "1") (pinfunction "1_1") (pintype "passive"))
      (node (ref "C68") (pin "2") (pinfunction "2_2") (pintype "passive"))
      (node (ref "C69") (pin "2") (pinfunction "2_2") (pintype "passive"))
      (node (ref "C7") (pin "1") (pinfunction "1_1") (pintype "passive"))
      (node (ref "C70") (pin "1") (pinfunction "1_1") (pintype "passive"))
      (node (ref "C71") (pin "1") (pinfunction "1_1") (pintype "passive"))
      (node (ref "C72") (pin "1") (pinfunction "1_1") (pintype "passive"))
      (node (ref "C73") (pin "1") (pinfunction "1_1") (pintype "passive"))
      (node (ref "C9") (pin "1") (pinfunction "1_1") (pintype "passive"))
      (node (ref "CN1") (pin "1") (pinfunction "1_1") (pintype "passive"))
      (node (ref "CN3") (pin "5") (pinfunction "5_5") (pintype "passive"))
      (node (ref "CN4") (pin "1") (pinfunction "1_1") (pintype "passive"))
      (node (ref "CN4") (pin "3") (pinfunction "3_3") (pintype "passive"))
      (node (ref "CN4") (pin "5") (pinfunction "5_5") (pintype "passive"))
      (node (ref "CN4") (pin "M1") (pinfunction "M1_M1") (pintype "passive"))
      (node (ref "CN4") (pin "M2") (pinfunction "M2_M2") (pintype "passive"))
      (node (ref "CN6") (pin "3") (pinfunction "3_3") (pintype "passive"))
      (node (ref "CN7") (pin "3") (pinfunction "3_3") (pintype "passive"))
      (node (ref "CN8") (pin "4") (pinfunction "4_4") (pintype "passive"))
      (node (ref "CN9") (pin "12") (pinfunction "B0_12") (pintype "passive"))
      (node (ref "CN9") (pin "13") (pinfunction "B1_13") (pintype "passive"))
      (node (ref "CN9") (pin "20") (pinfunction "G0_20") (pintype "passive"))
      (node (ref "CN9") (pin "21") (pinfunction "G1_21") (pintype "passive"))
      (node (ref "CN9") (pin "28") (pinfunction "R0_28") (pintype "passive"))
      (node (ref "CN9") (pin "29") (pinfunction "R1_29") (pintype "passive"))
      (node (ref "CN9") (pin "53") (pinfunction "DGND_53") (pintype "passive"))
      (node (ref "CN9") (pin "54") (pinfunction "AVSS_54") (pintype "passive"))
      (node (ref "D2") (pin "1") (pinfunction "A_1") (pintype "passive"))
      (node (ref "E1") (pin "2") (pinfunction "2_2") (pintype "passive"))
      (node (ref "E10") (pin "2") (pinfunction "2_2") (pintype "passive"))
      (node (ref "E11") (pin "2") (pinfunction "2_2") (pintype "passive"))
      (node (ref "E12") (pin "2") (pinfunction "2_2") (pintype "passive"))
      (node (ref "E13") (pin "2") (pinfunction "2_2") (pintype "passive"))
      (node (ref "E14") (pin "2") (pinfunction "2_2") (pintype "passive"))
      (node (ref "E15") (pin "2") (pinfunction "2_2") (pintype "passive"))
      (node (ref "E16") (pin "2") (pinfunction "2_2") (pintype "passive"))
      (node (ref "E2") (pin "2") (pinfunction "2_2") (pintype "passive"))
      (node (ref "E3") (pin "2") (pinfunction "2_2") (pintype "passive"))
      (node (ref "E4") (pin "2") (pinfunction "2_2") (pintype "passive"))
      (node (ref "E5") (pin "2") (pinfunction "2_2") (pintype "passive"))
      (node (ref "E6") (pin "2") (pinfunction "2_2") (pintype "passive"))
      (node (ref "E7") (pin "2") (pinfunction "2_2") (pintype "passive"))
      (node (ref "E8") (pin "2") (pinfunction "2_2") (pintype "passive"))
      (node (ref "E9") (pin "2") (pinfunction "2_2") (pintype "passive"))
      (node (ref "FB5") (pin "1") (pinfunction "1_1") (pintype "passive"))
      (node (ref "GND") (pin "1") (pinfunction "50_1") (pintype "passive"))
      (node (ref "GND1") (pin "1") (pinfunction "50_1") (pintype "passive"))
      (node (ref "GND2") (pin "1") (pinfunction "50_1") (pintype "passive"))
      (node (ref "R1") (pin "2") (pinfunction "2_2") (pintype "passive"))
      (node (ref "R12") (pin "2") (pinfunction "2_2") (pintype "passive"))
      (node (ref "R15") (pin "1") (pinfunction "1_1") (pintype "passive"))
      (node (ref "R18") (pin "1") (pinfunction "1_1") (pintype "passive"))
      (node (ref "R19") (pin "1") (pinfunction "1_1") (pintype "passive"))
      (node (ref "R2") (pin "1") (pinfunction "1_1") (pintype "passive"))
      (node (ref "R20") (pin "2") (pinfunction "2_2") (pintype "passive"))
      (node (ref "R21") (pin "2") (pinfunction "2_2") (pintype "passive"))
      (node (ref "R28") (pin "1") (pinfunction "1_1") (pintype "passive"))
      (node (ref "R38") (pin "2") (pinfunction "2_2") (pintype "passive"))
      (node (ref "R39") (pin "2") (pinfunction "2_2") (pintype "passive"))
      (node (ref "R4") (pin "1") (pinfunction "1_1") (pintype "passive"))
      (node (ref "U1") (pin "74") (pinfunction "TVGND_74") (pintype "passive"))
      (node (ref "U1") (pin "89") (pinfunction "GND_89") (pintype "passive"))
      (node (ref "U10") (pin "2") (pinfunction "GND_2") (pintype "passive"))
      (node (ref "U11") (pin "2") (pinfunction "GND_2") (pintype "passive"))
      (node (ref "U12") (pin "1") (pintype "passive"))
      (node (ref "U2") (pin "1") (pinfunction "G_1") (pintype "passive"))
      (node (ref "U3") (pin "7") (pinfunction "GND_7") (pintype "passive"))
      (node (ref "U4") (pin "4") (pinfunction "VSS_4") (pintype "passive"))
      (node (ref "U5") (pin "2") (pinfunction "GND_2") (pintype "passive"))
      (node (ref "U6") (pin "7") (pinfunction "GND_7") (pintype "passive"))
      (node (ref "U7") (pin "4") (pinfunction "VSS_4") (pintype "passive"))
      (node (ref "U8") (pin "2") (pinfunction "GND_2") (pintype "passive"))
      (node (ref "U9") (pin "2") (pinfunction "GND_2") (pintype "passive"))
      (node (ref "X1") (pin "2") (pinfunction "GND_2") (pintype "passive"))
      (node (ref "X1") (pin "3") (pinfunction "GND_3") (pintype "passive"))
      (node (ref "X2") (pin "2") (pinfunction "GND_2") (pintype "power_in"))
      (node (ref "X2") (pin "4") (pinfunction "GND_4") (pintype "power_in"))
    )
    (net (code "97") (name "HPVCC") (class "Default")
      (node (ref "C17") (pin "2") (pinfunction "2_2") (pintype "passive"))
      (node (ref "U1") (pin "4") (pinfunction "HPVCC_4") (pintype "passive"))
    )
    (net (code "98") (name "Net-(C12-Pad1)") (class "Default")
      (node (ref "C12") (pin "1") (pinfunction "1_1") (pintype "passive"))
      (node (ref "R11") (pin "1") (pinfunction "1_1") (pintype "passive"))
    )
    (net (code "99") (name "Net-(C13-Pad1)") (class "Default")
      (node (ref "C13") (pin "1") (pinfunction "1_1") (pintype "passive"))
      (node (ref "R13") (pin "1") (pinfunction "1_1") (pintype "passive"))
    )
    (net (code "100") (name "Net-(C57-Pad1)") (class "Default")
      (node (ref "C57") (pin "1") (pinfunction "1_1") (pintype "passive"))
      (node (ref "R4") (pin "2") (pinfunction "2_2") (pintype "passive"))
    )
    (net (code "101") (name "Net-(C58-Pad1)") (class "Default")
      (node (ref "C58") (pin "1") (pinfunction "1_1") (pintype "passive"))
      (node (ref "C59") (pin "2") (pinfunction "2_2") (pintype "passive"))
      (node (ref "R34") (pin "1") (pinfunction "1_1") (pintype "passive"))
    )
    (net (code "102") (name "Net-(C67-Pad1)") (class "Default")
      (node (ref "C67") (pin "1") (pinfunction "1_1") (pintype "passive"))
      (node (ref "R37") (pin "1") (pinfunction "1_1") (pintype "passive"))
    )
    (net (code "103") (name "Net-(C68-Pad1)") (class "Default")
      (node (ref "C68") (pin "1") (pinfunction "1_1") (pintype "passive"))
      (node (ref "L5") (pin "1") (pinfunction "1_1") (pintype "passive"))
      (node (ref "R37") (pin "2") (pinfunction "2_2") (pintype "passive"))
    )
    (net (code "104") (name "Net-(D4-K)") (class "Default")
      (node (ref "CN8") (pin "5") (pinfunction "5_5") (pintype "passive"))
      (node (ref "D4") (pin "2") (pinfunction "K_2") (pintype "output"))
      (node (ref "E3") (pin "1") (pinfunction "1_1") (pintype "passive"))
    )
    (net (code "105") (name "Net-(D9-A)") (class "Default")
      (node (ref "D9") (pin "1") (pinfunction "A_1") (pintype "input"))
      (node (ref "U1") (pin "41") (pinfunction "CSI_D5_/_PE8_41") (pintype "passive"))
    )
    (net (code "106") (name "Net-(U5-BST)") (class "Default")
      (node (ref "C27") (pin "2") (pinfunction "2_2") (pintype "passive"))
      (node (ref "U5") (pin "1") (pinfunction "BST_1") (pintype "passive"))
    )
    (net (code "107") (name "Net-(U5-FB)") (class "Default")
      (node (ref "R14") (pin "1") (pinfunction "1_1") (pintype "passive"))
      (node (ref "R15") (pin "2") (pinfunction "2_2") (pintype "passive"))
      (node (ref "U5") (pin "3") (pinfunction "FB_3") (pintype "passive"))
    )
    (net (code "108") (name "Net-(U6-BYPASS)") (class "Default")
      (node (ref "C51") (pin "1") (pinfunction "1_1") (pintype "passive"))
      (node (ref "U6") (pin "2") (pinfunction "BYPASS_2") (pintype "passive"))
    )
    (net (code "109") (name "Net-(U6-IN+)") (class "Default")
      (node (ref "R11") (pin "2") (pinfunction "2_2") (pintype "passive"))
      (node (ref "U6") (pin "4") (pinfunction "IN+_4") (pintype "passive"))
    )
    (net (code "110") (name "Net-(U6-IN-)") (class "Default")
      (node (ref "R13") (pin "2") (pinfunction "2_2") (pintype "passive"))
      (node (ref "U6") (pin "3") (pinfunction "IN-_3") (pintype "passive"))
    )
    (net (code "111") (name "Net-(U7-OSCI)") (class "Default")
      (node (ref "C52") (pin "1") (pinfunction "1_1") (pintype "passive"))
      (node (ref "U7") (pin "1") (pinfunction "OSCI_1") (pintype "passive"))
      (node (ref "X1") (pin "1") (pinfunction "OSC1_1") (pintype "passive"))
    )
    (net (code "112") (name "Net-(U7-OSCO)") (class "Default")
      (node (ref "C53") (pin "1") (pinfunction "1_1") (pintype "passive"))
      (node (ref "U7") (pin "2") (pinfunction "OSCO_2") (pintype "passive"))
      (node (ref "X1") (pin "4") (pinfunction "OSC2_4") (pintype "passive"))
    )
    (net (code "113") (name "Net-(U8-BST)") (class "Default")
      (node (ref "C44") (pin "2") (pinfunction "2_2") (pintype "passive"))
      (node (ref "U8") (pin "1") (pinfunction "BST_1") (pintype "passive"))
    )
    (net (code "114") (name "Net-(U8-FB)") (class "Default")
      (node (ref "R16") (pin "1") (pinfunction "1_1") (pintype "passive"))
      (node (ref "R18") (pin "2") (pinfunction "2_2") (pintype "passive"))
      (node (ref "U8") (pin "3") (pinfunction "FB_3") (pintype "passive"))
    )
    (net (code "115") (name "Net-(U9-BST)") (class "Default")
      (node (ref "C31") (pin "1") (pinfunction "1_1") (pintype "passive"))
      (node (ref "U9") (pin "1") (pinfunction "BST_1") (pintype "passive"))
    )
    (net (code "116") (name "Net-(U9-FB)") (class "Default")
      (node (ref "R17") (pin "1") (pinfunction "1_1") (pintype "passive"))
      (node (ref "R19") (pin "2") (pinfunction "2_2") (pintype "passive"))
      (node (ref "U9") (pin "3") (pinfunction "FB_3") (pintype "passive"))
    )
    (net (code "117") (name "Net-(U10-EN)") (class "Default")
      (node (ref "C40") (pin "1") (pinfunction "1_1") (pintype "passive"))
      (node (ref "R20") (pin "1") (pinfunction "1_1") (pintype "passive"))
      (node (ref "R27") (pin "2") (pinfunction "2_2") (pintype "passive"))
      (node (ref "U10") (pin "4") (pinfunction "EN_4") (pintype "passive"))
    )
    (net (code "118") (name "Net-(U11-BP)") (class "Default")
      (node (ref "C71") (pin "2") (pinfunction "2_2") (pintype "passive"))
      (node (ref "U11") (pin "4") (pinfunction "BP_4") (pintype "passive"))
    )
    (net (code "119") (name "Net-(U11-EN)") (class "Default")
      (node (ref "R40") (pin "1") (pinfunction "1_1") (pintype "passive"))
      (node (ref "U11") (pin "3") (pinfunction "EN_3") (pintype "passive"))
    )
    (net (code "120") (name "SPK_VCC") (class "Default")
      (node (ref "C11") (pin "1") (pinfunction "1_1") (pintype "passive"))
      (node (ref "C15") (pin "1") (pinfunction "1_1") (pintype "passive"))
      (node (ref "FB4") (pin "1") (pinfunction "1_1") (pintype "passive"))
      (node (ref "U6") (pin "6") (pinfunction "VDD_6") (pintype "passive"))
    )
    (net (code "121") (name "VBAT") (class "Default")
      (node (ref "C26") (pin "2") (pinfunction "2_2") (pintype "passive"))
      (node (ref "C30") (pin "2") (pinfunction "2_2") (pintype "passive"))
      (node (ref "C43") (pin "2") (pinfunction "2_2") (pintype "passive"))
      (node (ref "C47") (pin "2") (pinfunction "2_2") (pintype "passive"))
      (node (ref "CN1") (pin "2") (pinfunction "2_2") (pintype "passive"))
      (node (ref "CN4") (pin "7") (pinfunction "7_7") (pintype "passive"))
      (node (ref "D1") (pin "2") (pinfunction "K_2") (pintype "passive"))
      (node (ref "D2") (pin "2") (pinfunction "K_2") (pintype "passive"))
      (node (ref "U2") (pin "2") (pinfunction "VIN_2") (pintype "passive"))
      (node (ref "U5") (pin "5") (pinfunction "VIN_5") (pintype "passive"))
      (node (ref "U8") (pin "5") (pinfunction "VIN_5") (pintype "passive"))
      (node (ref "U9") (pin "5") (pinfunction "VIN_5") (pintype "passive"))
    )
    (net (code "122") (name "VCC-DRAM-AP") (class "Default")
      (node (ref "C1") (pin "2") (pinfunction "2_2") (pintype "passive"))
      (node (ref "C2") (pin "1") (pinfunction "1_1") (pintype "passive"))
      (node (ref "C3") (pin "2") (pinfunction "2_2") (pintype "passive"))
      (node (ref "C4") (pin "2") (pinfunction "2_2") (pintype "passive"))
      (node (ref "C45") (pin "1") (pinfunction "1_1") (pintype "passive"))
      (node (ref "C46") (pin "2") (pinfunction "2_2") (pintype "passive"))
      (node (ref "L3") (pin "2") (pinfunction "2_2") (pintype "passive"))
      (node (ref "R16") (pin "2") (pinfunction "2_2") (pintype "passive"))
      (node (ref "R26") (pin "2") (pinfunction "2_2") (pintype "passive"))
      (node (ref "U1") (pin "30") (pinfunction "DRAMVCC1_30") (pintype "passive"))
      (node (ref "U1") (pin "31") (pinfunction "DRAMVCC2_31") (pintype "passive"))
      (node (ref "U1") (pin "32") (pinfunction "DRAMVCC3_32") (pintype "passive"))
      (node (ref "U1") (pin "34") (pinfunction "DRAMVCC4_34") (pintype "passive"))
      (node (ref "U1") (pin "36") (pinfunction "DRAMVCC5_36") (pintype "passive"))
    )
    (net (code "123") (name "VCC-IO") (class "Default")
      (node (ref "C20") (pin "2") (pinfunction "2_2") (pintype "passive"))
      (node (ref "C21") (pin "1") (pinfunction "1_1") (pintype "passive"))
      (node (ref "C22") (pin "2") (pinfunction "2_2") (pintype "passive"))
      (node (ref "C23") (pin "2") (pinfunction "2_2") (pintype "passive"))
      (node (ref "C25") (pin "2") (pinfunction "2_2") (pintype "passive"))
      (node (ref "C28") (pin "1") (pinfunction "1_1") (pintype "passive"))
      (node (ref "C29") (pin "2") (pinfunction "2_2") (pintype "passive"))
      (node (ref "C32") (pin "2") (pinfunction "2_2") (pintype "passive"))
      (node (ref "C38") (pin "2") (pinfunction "2_2") (pintype "passive"))
      (node (ref "C61") (pin "1") (pinfunction "1_1") (pintype "passive"))
      (node (ref "C70") (pin "2") (pinfunction "2_2") (pintype "passive"))
      (node (ref "FB2") (pin "2") (pinfunction "2_2") (pintype "passive"))
      (node (ref "FB3") (pin "2") (pinfunction "2_2") (pintype "passive"))
      (node (ref "FB4") (pin "2") (pinfunction "2_2") (pintype "passive"))
      (node (ref "L1") (pin "2") (pinfunction "2_2") (pintype "passive"))
      (node (ref "L4") (pin "1") (pinfunction "1_1") (pintype "passive"))
      (node (ref "R10") (pin "2") (pinfunction "2_2") (pintype "passive"))
      (node (ref "R14") (pin "2") (pinfunction "2_2") (pintype "passive"))
      (node (ref "R31") (pin "2") (pinfunction "2_2") (pintype "passive"))
      (node (ref "R32") (pin "2") (pinfunction "2_2") (pintype "passive"))
      (node (ref "R40") (pin "2") (pinfunction "2_2") (pintype "passive"))
      (node (ref "R5") (pin "2") (pinfunction "2_2") (pintype "passive"))
      (node (ref "R6") (pin "2") (pinfunction "2_2") (pintype "passive"))
      (node (ref "R7") (pin "2") (pinfunction "2_2") (pintype "passive"))
      (node (ref "R8") (pin "1") (pinfunction "1_1") (pintype "passive"))
      (node (ref "R9") (pin "2") (pinfunction "2_2") (pintype "passive"))
      (node (ref "U1") (pin "20") (pinfunction "VCC2_20") (pintype "passive"))
      (node (ref "U1") (pin "5") (pinfunction "VCC1_5") (pintype "passive"))
      (node (ref "U1") (pin "50") (pinfunction "VCC3_50") (pintype "passive"))
      (node (ref "U1") (pin "67") (pinfunction "UVCC_67") (pintype "passive"))
      (node (ref "U10") (pin "6") (pinfunction "VDD_6") (pintype "passive"))
      (node (ref "U11") (pin "1") (pinfunction "IN_1") (pintype "passive"))
      (node (ref "U12") (pin "3") (pinfunction "IN_3") (pintype "passive"))
      (node (ref "U4") (pin "8") (pinfunction "VCC_8") (pintype "passive"))
    )
    (net (code "124") (name "VCC-TV") (class "Default")
      (node (ref "C24") (pin "2") (pinfunction "2_2") (pintype "passive"))
      (node (ref "C72") (pin "2") (pinfunction "2_2") (pintype "passive"))
      (node (ref "C73") (pin "2") (pinfunction "2_2") (pintype "passive"))
      (node (ref "FB2") (pin "1") (pinfunction "1_1") (pintype "passive"))
      (node (ref "U1") (pin "73") (pinfunction "TVVCC_73") (pintype "passive"))
      (node (ref "U11") (pin "5") (pinfunction "OUT_5") (pintype "passive"))
    )
    (net (code "125") (name "VCC_1V1") (class "Default")
      (node (ref "C16") (pin "1") (pinfunction "1_1") (pintype "passive"))
      (node (ref "C18") (pin "2") (pinfunction "2_2") (pintype "passive"))
      (node (ref "C19") (pin "2") (pinfunction "2_2") (pintype "passive"))
      (node (ref "C33") (pin "1") (pinfunction "1_1") (pintype "passive"))
      (node (ref "C34") (pin "2") (pinfunction "2_2") (pintype "passive"))
      (node (ref "C56") (pin "2") (pinfunction "2_2") (pintype "passive"))
      (node (ref "L2") (pin "2") (pinfunction "2_2") (pintype "passive"))
      (node (ref "R17") (pin "2") (pinfunction "2_2") (pintype "passive"))
      (node (ref "U1") (pin "22") (pinfunction "VDD2_22") (pintype "passive"))
      (node (ref "U1") (pin "35") (pinfunction "VDD3_35") (pintype "passive"))
      (node (ref "U1") (pin "71") (pinfunction "VDD1_71") (pintype "passive"))
    )
    (net (code "126") (name "VCC_2V8") (class "Default")
      (node (ref "C62") (pin "1") (pinfunction "1_1") (pintype "passive"))
      (node (ref "FB1") (pin "2") (pinfunction "2_2") (pintype "passive"))
      (node (ref "U12") (pin "2") (pinfunction "OUT_2") (pintype "passive"))
    )
    (net (code "127") (name "VCC_LCD") (class "Default")
      (node (ref "C41") (pin "1") (pinfunction "1_1") (pintype "passive"))
      (node (ref "C42") (pin "1") (pinfunction "1_1") (pintype "passive"))
      (node (ref "CN9") (pin "41") (pinfunction "VCC_41") (pintype "passive"))
      (node (ref "CN9") (pin "42") (pinfunction "VCC_42") (pintype "passive"))
      (node (ref "FB3") (pin "1") (pinfunction "1_1") (pintype "passive"))
      (node (ref "R29") (pin "2") (pinfunction "2_2") (pintype "passive"))
    )
    (net (code "128") (name "VCC_MCU") (class "Default")
      (node (ref "C14") (pin "2") (pinfunction "2_2") (pintype "passive"))
      (node (ref "C48") (pin "2") (pinfunction "2_2") (pintype "passive"))
      (node (ref "C50") (pin "2") (pinfunction "2_2") (pintype "passive"))
      (node (ref "CN3") (pin "3") (pinfunction "3_3") (pintype "passive"))
      (node (ref "E10") (pin "1") (pinfunction "1_1") (pintype "passive"))
      (node (ref "U2") (pin "3") (pinfunction "VOUT_3") (pintype "passive"))
      (node (ref "U3") (pin "9") (pinfunction "VDD_9") (pintype "passive"))
      (node (ref "U7") (pin "8") (pinfunction "VDD_8") (pintype "passive"))
    )
    (net (code "129") (name "VUSB") (class "Default")
      (node (ref "CN8") (pin "1") (pinfunction "1_1") (pintype "passive"))
      (node (ref "D1") (pin "1") (pinfunction "A_1") (pintype "passive"))
      (node (ref "D8") (pin "1") (pinfunction "1A_1") (pintype "passive"))
      (node (ref "E8") (pin "1") (pinfunction "1_1") (pintype "passive"))
    )
    (net (code "130") (name "unconnected-(CN5-Pad3)") (class "Default")
      (node (ref "CN5") (pin "3") (pinfunction "3_3") (pintype "passive+no_connect"))
    )
    (net (code "131") (name "unconnected-(CN5-Pad4)") (class "Default")
      (node (ref "CN5") (pin "4") (pinfunction "4_4") (pintype "passive+no_connect"))
    )
    (net (code "132") (name "unconnected-(CN9-CS-Pad9)") (class "Default")
      (node (ref "CN9") (pin "9") (pinfunction "CS_9") (pintype "passive+no_connect"))
    )
    (net (code "133") (name "unconnected-(CN9-NC-Pad39)") (class "Default")
      (node (ref "CN9") (pin "39") (pinfunction "NC_39") (pintype "passive+no_connect"))
    )
    (net (code "134") (name "unconnected-(CN9-NC-Pad40)") (class "Default")
      (node (ref "CN9") (pin "40") (pinfunction "NC_40") (pintype "passive+no_connect"))
    )
    (net (code "135") (name "unconnected-(CN9-NC-Pad45)") (class "Default")
      (node (ref "CN9") (pin "45") (pinfunction "NC_45") (pintype "passive+no_connect"))
    )
    (net (code "136") (name "unconnected-(CN9-NC-Pad46)") (class "Default")
      (node (ref "CN9") (pin "46") (pinfunction "NC_46") (pintype "passive+no_connect"))
    )
    (net (code "137") (name "unconnected-(CN9-NC-Pad47)") (class "Default")
      (node (ref "CN9") (pin "47") (pinfunction "NC_47") (pintype "passive+no_connect"))
    )
    (net (code "138") (name "unconnected-(CN9-NC-Pad48)") (class "Default")
      (node (ref "CN9") (pin "48") (pinfunction "NC_48") (pintype "passive+no_connect"))
    )
    (net (code "139") (name "unconnected-(CN9-NC-Pad49)") (class "Default")
      (node (ref "CN9") (pin "49") (pinfunction "NC_49") (pintype "passive+no_connect"))
    )
    (net (code "140") (name "unconnected-(CN9-NC-Pad50)") (class "Default")
      (node (ref "CN9") (pin "50") (pinfunction "NC_50") (pintype "passive+no_connect"))
    )
    (net (code "141") (name "unconnected-(CN9-NC-Pad51)") (class "Default")
      (node (ref "CN9") (pin "51") (pinfunction "NC_51") (pintype "passive+no_connect"))
    )
    (net (code "142") (name "unconnected-(CN9-SCL-Pad10)") (class "Default")
      (node (ref "CN9") (pin "10") (pinfunction "SCL_10") (pintype "passive+no_connect"))
    )
    (net (code "143") (name "unconnected-(CN9-SDI-Pad11)") (class "Default")
      (node (ref "CN9") (pin "11") (pinfunction "SDI_11") (pintype "passive+no_connect"))
    )
    (net (code "144") (name "unconnected-(U1-CSI_D3_{slash}_PE6-Pad43)") (class "Default")
      (node (ref "U1") (pin "43") (pinfunction "CSI_D3_/_PE6_43") (pintype "passive+no_connect"))
    )
    (net (code "145") (name "unconnected-(U1-CSI_D4_{slash}_PE7-Pad42)") (class "Default")
      (node (ref "U1") (pin "42") (pinfunction "CSI_D4_/_PE7_42") (pintype "passive+no_connect"))
    )
    (net (code "146") (name "unconnected-(U1-CSI_D6_{slash}_PE9-Pad40)") (class "Default")
      (node (ref "U1") (pin "40") (pinfunction "CSI_D6_/_PE9_40") (pintype "passive+no_connect"))
    )
    (net (code "147") (name "unconnected-(U1-CSI_D7_{slash}_PE10-Pad39)") (class "Default")
      (node (ref "U1") (pin "39") (pinfunction "CSI_D7_/_PE10_39") (pintype "passive+no_connect"))
    )
    (net (code "148") (name "unconnected-(U1-CSI_PCLK_{slash}_PE2-Pad47)") (class "Default")
      (node (ref "U1") (pin "47") (pinfunction "CSI_PCLK_/_PE2_47") (pintype "passive+no_connect"))
    )
    (net (code "149") (name "unconnected-(U1-FMINL-Pad84)") (class "Default")
      (node (ref "U1") (pin "84") (pinfunction "FMINL_84") (pintype "passive+no_connect"))
    )
    (net (code "150") (name "unconnected-(U1-FMINR-Pad85)") (class "Default")
      (node (ref "U1") (pin "85") (pinfunction "FMINR_85") (pintype "passive+no_connect"))
    )
    (net (code "151") (name "unconnected-(U1-HPL-Pad1)") (class "Default")
      (node (ref "U1") (pin "1") (pinfunction "HPL_1") (pintype "passive+no_connect"))
    )
    (net (code "152") (name "unconnected-(U1-LINL-Pad86)") (class "Default")
      (node (ref "U1") (pin "86") (pinfunction "LINL_86") (pintype "passive+no_connect"))
    )
    (net (code "153") (name "unconnected-(U1-LRADCIN-Pad79)") (class "Default")
      (node (ref "U1") (pin "79") (pinfunction "LRADCIN_79") (pintype "passive+no_connect"))
    )
    (net (code "154") (name "unconnected-(U1-TVIN1-Pad77)") (class "Default")
      (node (ref "U1") (pin "77") (pinfunction "TVIN1_77") (pintype "passive+no_connect"))
    )
    (net (code "155") (name "unconnected-(U1-TVOUT-Pad72)") (class "Default")
      (node (ref "U1") (pin "72") (pinfunction "TVOUT_72") (pintype "passive+no_connect"))
    )
    (net (code "156") (name "unconnected-(U3-P0.0{slash}PWM3{slash}IC3{slash}MOSI{slash}T1-Pad16)") (class "Default")
      (node (ref "U3") (pin "16") (pinfunction "P0.0/PWM3/IC3/MOSI/T1_16") (pintype "passive+no_connect"))
    )
    (net (code "157") (name "unconnected-(U3-P0.1{slash}PWM4{slash}IC4{slash}MISO-Pad17)") (class "Default")
      (node (ref "U3") (pin "17") (pinfunction "P0.1/PWM4/IC4/MISO_17") (pintype "passive+no_connect"))
    )
    (net (code "158") (name "unconnected-(U3-P0.3{slash}PWM5{slash}IC5{slash}AIN6-Pad19)") (class "Default")
      (node (ref "U3") (pin "19") (pinfunction "P0.3/PWM5/IC5/AIN6_19") (pintype "passive+no_connect"))
    )
    (net (code "159") (name "unconnected-(U3-P1.1{slash}PWM1{slash}IC1{slash}AIN7{slash}CLO-Pad14)") (class "Default")
      (node (ref "U3") (pin "14") (pinfunction "P1.1/PWM1/IC1/AIN7/CLO_14") (pintype "passive+no_connect"))
    )
    (net (code "160") (name "unconnected-(U3-P1.2{slash}PWM0{slash}IC0-Pad13)") (class "Default")
      (node (ref "U3") (pin "13") (pinfunction "P1.2/PWM0/IC0_13") (pintype "passive+no_connect"))
    )
    (net (code "161") (name "unconnected-(U3-P3.0{slash}AIN1{slash}OSCIN{slash}~{INT0}-Pad5)") (class "Default")
      (node (ref "U3") (pin "5") (pinfunction "P3.0/AIN1/OSCIN/~{INT0}_5") (pintype "passive+no_connect"))
    )
    (net (code "162") (name "unconnected-(U7-CLKOUT-Pad7)") (class "Default")
      (node (ref "U7") (pin "7") (pinfunction "CLKOUT_7") (pintype "passive+no_connect"))
    )
    (net (code "163") (name "unconnected-(U7-~{INT}-Pad3)") (class "Default")
      (node (ref "U7") (pin "3") (pinfunction "~{INT}_3") (pintype "passive"))
    )
  )
)
